# Smart_Light_Panel3.net
KiCad netlist of a schematic drawn in EAGLE
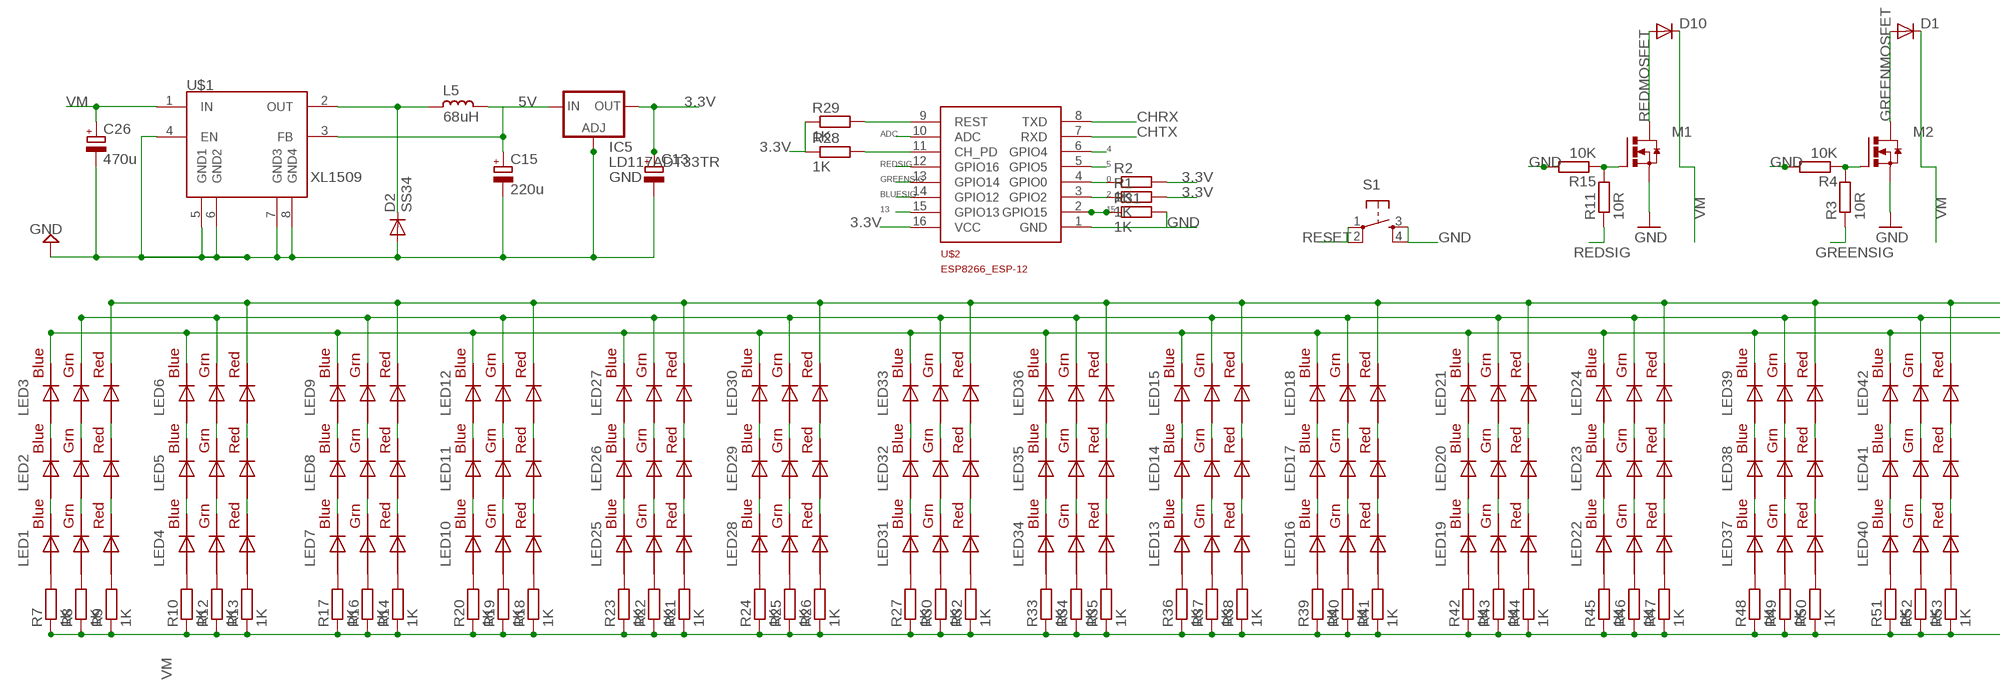
[diagram p0: schematic, sheet 1, part 1 of 2]
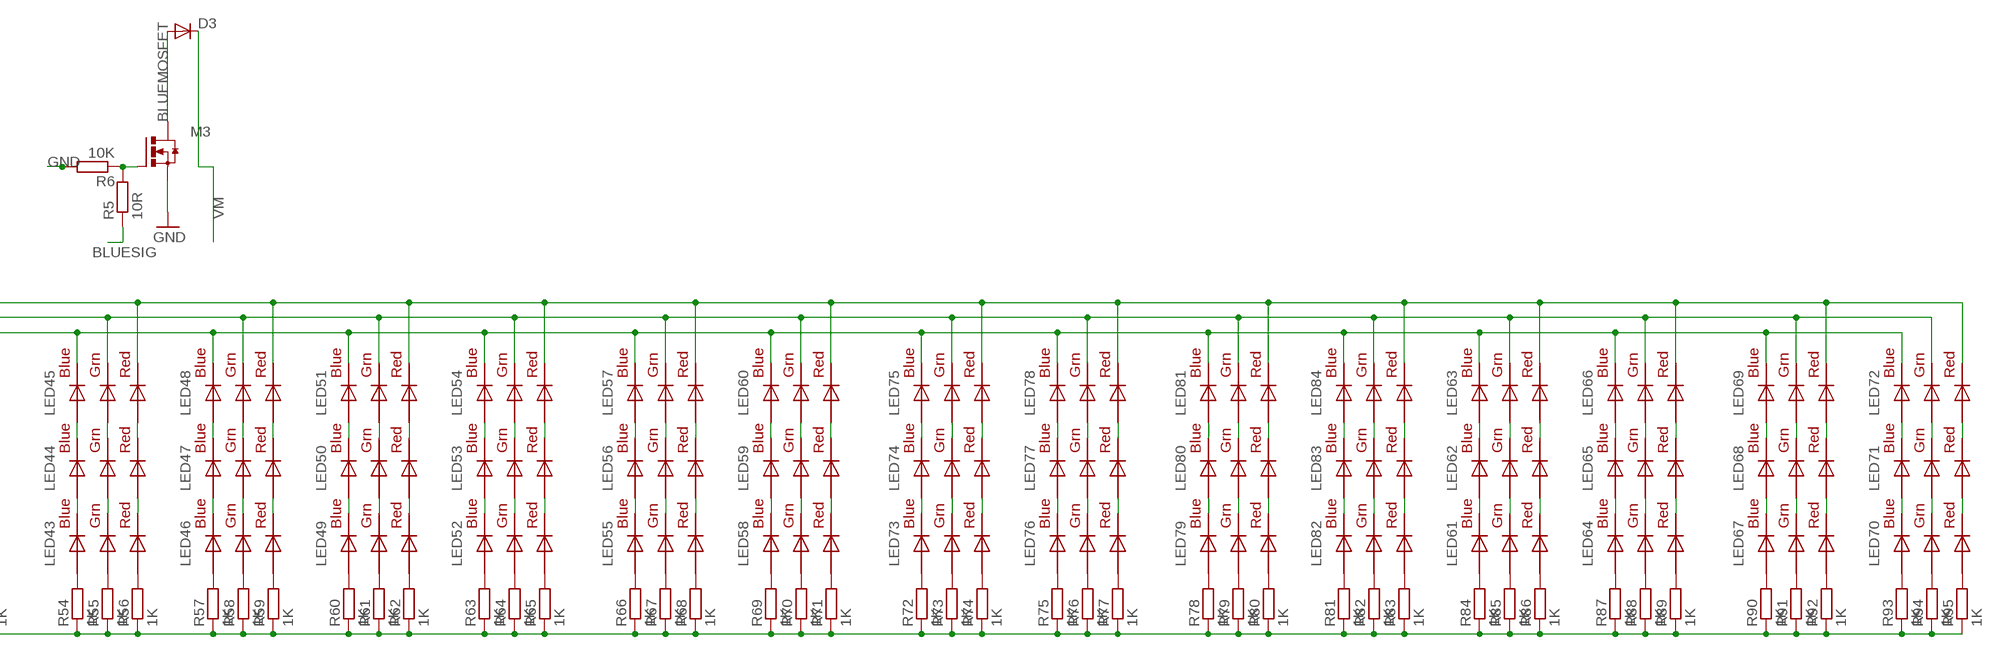
[diagram p1: schematic, sheet 1, part 2 of 2]

(export (version "E")
  (design (tool "Eeschema 10.0.6"))
  (components
    (comp (ref "C13")
      (value "CPOL-EUE2.5-7")
      (footprint "eagle-import:E2,5-7")
      (libsource (lib "eagle-import") (part "CPOL-EUE2.5-7"))
    )
    (comp (ref "C15")
      (value "220u")
      (footprint "eagle-import:E2,5-7")
      (libsource (lib "eagle-import") (part "CPOL-EUE2.5-7"))
    )
    (comp (ref "C26")
      (value "470u")
      (footprint "eagle-import:E2,5-7")
      (libsource (lib "eagle-import") (part "CPOL-EUE2.5-7"))
    )
    (comp (ref "D1")
      (value "DIODESMA-ALT")
      (footprint "eagle-import:SMA-DIODE_ALT")
      (libsource (lib "eagle-import") (part "DIODESMA-ALT"))
    )
    (comp (ref "D2")
      (value "SS34")
      (footprint "eagle-import:DO-214AC")
      (libsource (lib "eagle-import") (part "DIODE-DO-214AC"))
    )
    (comp (ref "D3")
      (value "DIODESMA-ALT")
      (footprint "eagle-import:SMA-DIODE_ALT")
      (libsource (lib "eagle-import") (part "DIODESMA-ALT"))
    )
    (comp (ref "D10")
      (value "DIODESMA-ALT")
      (footprint "eagle-import:SMA-DIODE_ALT")
      (libsource (lib "eagle-import") (part "DIODESMA-ALT"))
    )
    (comp (ref "IC5")
      (value "LD117ADT33TR")
      (footprint "eagle-import:DPACK")
      (libsource (lib "eagle-import") (part "LD117A?DT33TR"))
    )
    (comp (ref "L5")
      (value "68uH")
      (footprint "eagle-import:CD75")
      (libsource (lib "eagle-import") (part "L_CD75"))
    )
    (comp (ref "LED1")
      (value "RGBLED5050")
      (footprint "eagle-import:RGBLED5050")
      (libsource (lib "eagle-import") (part "RGBLED5050"))
    )
    (comp (ref "LED2")
      (value "RGBLED5050")
      (footprint "eagle-import:RGBLED5050")
      (libsource (lib "eagle-import") (part "RGBLED5050"))
    )
    (comp (ref "LED3")
      (value "RGBLED5050")
      (footprint "eagle-import:RGBLED5050")
      (libsource (lib "eagle-import") (part "RGBLED5050"))
    )
    (comp (ref "LED4")
      (value "RGBLED5050")
      (footprint "eagle-import:RGBLED5050")
      (libsource (lib "eagle-import") (part "RGBLED5050"))
    )
    (comp (ref "LED5")
      (value "RGBLED5050")
      (footprint "eagle-import:RGBLED5050")
      (libsource (lib "eagle-import") (part "RGBLED5050"))
    )
    (comp (ref "LED6")
      (value "RGBLED5050")
      (footprint "eagle-import:RGBLED5050")
      (libsource (lib "eagle-import") (part "RGBLED5050"))
    )
    (comp (ref "LED7")
      (value "RGBLED5050")
      (footprint "eagle-import:RGBLED5050")
      (libsource (lib "eagle-import") (part "RGBLED5050"))
    )
    (comp (ref "LED8")
      (value "RGBLED5050")
      (footprint "eagle-import:RGBLED5050")
      (libsource (lib "eagle-import") (part "RGBLED5050"))
    )
    (comp (ref "LED9")
      (value "RGBLED5050")
      (footprint "eagle-import:RGBLED5050")
      (libsource (lib "eagle-import") (part "RGBLED5050"))
    )
    (comp (ref "LED10")
      (value "RGBLED5050")
      (footprint "eagle-import:RGBLED5050")
      (libsource (lib "eagle-import") (part "RGBLED5050"))
    )
    (comp (ref "LED11")
      (value "RGBLED5050")
      (footprint "eagle-import:RGBLED5050")
      (libsource (lib "eagle-import") (part "RGBLED5050"))
    )
    (comp (ref "LED12")
      (value "RGBLED5050")
      (footprint "eagle-import:RGBLED5050")
      (libsource (lib "eagle-import") (part "RGBLED5050"))
    )
    (comp (ref "LED13")
      (value "RGBLED5050")
      (footprint "eagle-import:RGBLED5050")
      (libsource (lib "eagle-import") (part "RGBLED5050"))
    )
    (comp (ref "LED14")
      (value "RGBLED5050")
      (footprint "eagle-import:RGBLED5050")
      (libsource (lib "eagle-import") (part "RGBLED5050"))
    )
    (comp (ref "LED15")
      (value "RGBLED5050")
      (footprint "eagle-import:RGBLED5050")
      (libsource (lib "eagle-import") (part "RGBLED5050"))
    )
    (comp (ref "LED16")
      (value "RGBLED5050")
      (footprint "eagle-import:RGBLED5050")
      (libsource (lib "eagle-import") (part "RGBLED5050"))
    )
    (comp (ref "LED17")
      (value "RGBLED5050")
      (footprint "eagle-import:RGBLED5050")
      (libsource (lib "eagle-import") (part "RGBLED5050"))
    )
    (comp (ref "LED18")
      (value "RGBLED5050")
      (footprint "eagle-import:RGBLED5050")
      (libsource (lib "eagle-import") (part "RGBLED5050"))
    )
    (comp (ref "LED19")
      (value "RGBLED5050")
      (footprint "eagle-import:RGBLED5050")
      (libsource (lib "eagle-import") (part "RGBLED5050"))
    )
    (comp (ref "LED20")
      (value "RGBLED5050")
      (footprint "eagle-import:RGBLED5050")
      (libsource (lib "eagle-import") (part "RGBLED5050"))
    )
    (comp (ref "LED21")
      (value "RGBLED5050")
      (footprint "eagle-import:RGBLED5050")
      (libsource (lib "eagle-import") (part "RGBLED5050"))
    )
    (comp (ref "LED22")
      (value "RGBLED5050")
      (footprint "eagle-import:RGBLED5050")
      (libsource (lib "eagle-import") (part "RGBLED5050"))
    )
    (comp (ref "LED23")
      (value "RGBLED5050")
      (footprint "eagle-import:RGBLED5050")
      (libsource (lib "eagle-import") (part "RGBLED5050"))
    )
    (comp (ref "LED24")
      (value "RGBLED5050")
      (footprint "eagle-import:RGBLED5050")
      (libsource (lib "eagle-import") (part "RGBLED5050"))
    )
    (comp (ref "LED25")
      (value "RGBLED5050")
      (footprint "eagle-import:RGBLED5050")
      (libsource (lib "eagle-import") (part "RGBLED5050"))
    )
    (comp (ref "LED26")
      (value "RGBLED5050")
      (footprint "eagle-import:RGBLED5050")
      (libsource (lib "eagle-import") (part "RGBLED5050"))
    )
    (comp (ref "LED27")
      (value "RGBLED5050")
      (footprint "eagle-import:RGBLED5050")
      (libsource (lib "eagle-import") (part "RGBLED5050"))
    )
    (comp (ref "LED28")
      (value "RGBLED5050")
      (footprint "eagle-import:RGBLED5050")
      (libsource (lib "eagle-import") (part "RGBLED5050"))
    )
    (comp (ref "LED29")
      (value "RGBLED5050")
      (footprint "eagle-import:RGBLED5050")
      (libsource (lib "eagle-import") (part "RGBLED5050"))
    )
    (comp (ref "LED30")
      (value "RGBLED5050")
      (footprint "eagle-import:RGBLED5050")
      (libsource (lib "eagle-import") (part "RGBLED5050"))
    )
    (comp (ref "LED31")
      (value "RGBLED5050")
      (footprint "eagle-import:RGBLED5050")
      (libsource (lib "eagle-import") (part "RGBLED5050"))
    )
    (comp (ref "LED32")
      (value "RGBLED5050")
      (footprint "eagle-import:RGBLED5050")
      (libsource (lib "eagle-import") (part "RGBLED5050"))
    )
    (comp (ref "LED33")
      (value "RGBLED5050")
      (footprint "eagle-import:RGBLED5050")
      (libsource (lib "eagle-import") (part "RGBLED5050"))
    )
    (comp (ref "LED34")
      (value "RGBLED5050")
      (footprint "eagle-import:RGBLED5050")
      (libsource (lib "eagle-import") (part "RGBLED5050"))
    )
    (comp (ref "LED35")
      (value "RGBLED5050")
      (footprint "eagle-import:RGBLED5050")
      (libsource (lib "eagle-import") (part "RGBLED5050"))
    )
    (comp (ref "LED36")
      (value "RGBLED5050")
      (footprint "eagle-import:RGBLED5050")
      (libsource (lib "eagle-import") (part "RGBLED5050"))
    )
    (comp (ref "LED37")
      (value "RGBLED5050")
      (footprint "eagle-import:RGBLED5050")
      (libsource (lib "eagle-import") (part "RGBLED5050"))
    )
    (comp (ref "LED38")
      (value "RGBLED5050")
      (footprint "eagle-import:RGBLED5050")
      (libsource (lib "eagle-import") (part "RGBLED5050"))
    )
    (comp (ref "LED39")
      (value "RGBLED5050")
      (footprint "eagle-import:RGBLED5050")
      (libsource (lib "eagle-import") (part "RGBLED5050"))
    )
    (comp (ref "LED40")
      (value "RGBLED5050")
      (footprint "eagle-import:RGBLED5050")
      (libsource (lib "eagle-import") (part "RGBLED5050"))
    )
    (comp (ref "LED41")
      (value "RGBLED5050")
      (footprint "eagle-import:RGBLED5050")
      (libsource (lib "eagle-import") (part "RGBLED5050"))
    )
    (comp (ref "LED42")
      (value "RGBLED5050")
      (footprint "eagle-import:RGBLED5050")
      (libsource (lib "eagle-import") (part "RGBLED5050"))
    )
    (comp (ref "LED43")
      (value "RGBLED5050")
      (footprint "eagle-import:RGBLED5050")
      (libsource (lib "eagle-import") (part "RGBLED5050"))
    )
    (comp (ref "LED44")
      (value "RGBLED5050")
      (footprint "eagle-import:RGBLED5050")
      (libsource (lib "eagle-import") (part "RGBLED5050"))
    )
    (comp (ref "LED45")
      (value "RGBLED5050")
      (footprint "eagle-import:RGBLED5050")
      (libsource (lib "eagle-import") (part "RGBLED5050"))
    )
    (comp (ref "LED46")
      (value "RGBLED5050")
      (footprint "eagle-import:RGBLED5050")
      (libsource (lib "eagle-import") (part "RGBLED5050"))
    )
    (comp (ref "LED47")
      (value "RGBLED5050")
      (footprint "eagle-import:RGBLED5050")
      (libsource (lib "eagle-import") (part "RGBLED5050"))
    )
    (comp (ref "LED48")
      (value "RGBLED5050")
      (footprint "eagle-import:RGBLED5050")
      (libsource (lib "eagle-import") (part "RGBLED5050"))
    )
    (comp (ref "LED49")
      (value "RGBLED5050")
      (footprint "eagle-import:RGBLED5050")
      (libsource (lib "eagle-import") (part "RGBLED5050"))
    )
    (comp (ref "LED50")
      (value "RGBLED5050")
      (footprint "eagle-import:RGBLED5050")
      (libsource (lib "eagle-import") (part "RGBLED5050"))
    )
    (comp (ref "LED51")
      (value "RGBLED5050")
      (footprint "eagle-import:RGBLED5050")
      (libsource (lib "eagle-import") (part "RGBLED5050"))
    )
    (comp (ref "LED52")
      (value "RGBLED5050")
      (footprint "eagle-import:RGBLED5050")
      (libsource (lib "eagle-import") (part "RGBLED5050"))
    )
    (comp (ref "LED53")
      (value "RGBLED5050")
      (footprint "eagle-import:RGBLED5050")
      (libsource (lib "eagle-import") (part "RGBLED5050"))
    )
    (comp (ref "LED54")
      (value "RGBLED5050")
      (footprint "eagle-import:RGBLED5050")
      (libsource (lib "eagle-import") (part "RGBLED5050"))
    )
    (comp (ref "LED55")
      (value "RGBLED5050")
      (footprint "eagle-import:RGBLED5050")
      (libsource (lib "eagle-import") (part "RGBLED5050"))
    )
    (comp (ref "LED56")
      (value "RGBLED5050")
      (footprint "eagle-import:RGBLED5050")
      (libsource (lib "eagle-import") (part "RGBLED5050"))
    )
    (comp (ref "LED57")
      (value "RGBLED5050")
      (footprint "eagle-import:RGBLED5050")
      (libsource (lib "eagle-import") (part "RGBLED5050"))
    )
    (comp (ref "LED58")
      (value "RGBLED5050")
      (footprint "eagle-import:RGBLED5050")
      (libsource (lib "eagle-import") (part "RGBLED5050"))
    )
    (comp (ref "LED59")
      (value "RGBLED5050")
      (footprint "eagle-import:RGBLED5050")
      (libsource (lib "eagle-import") (part "RGBLED5050"))
    )
    (comp (ref "LED60")
      (value "RGBLED5050")
      (footprint "eagle-import:RGBLED5050")
      (libsource (lib "eagle-import") (part "RGBLED5050"))
    )
    (comp (ref "LED61")
      (value "RGBLED5050")
      (footprint "eagle-import:RGBLED5050")
      (libsource (lib "eagle-import") (part "RGBLED5050"))
    )
    (comp (ref "LED62")
      (value "RGBLED5050")
      (footprint "eagle-import:RGBLED5050")
      (libsource (lib "eagle-import") (part "RGBLED5050"))
    )
    (comp (ref "LED63")
      (value "RGBLED5050")
      (footprint "eagle-import:RGBLED5050")
      (libsource (lib "eagle-import") (part "RGBLED5050"))
    )
    (comp (ref "LED64")
      (value "RGBLED5050")
      (footprint "eagle-import:RGBLED5050")
      (libsource (lib "eagle-import") (part "RGBLED5050"))
    )
    (comp (ref "LED65")
      (value "RGBLED5050")
      (footprint "eagle-import:RGBLED5050")
      (libsource (lib "eagle-import") (part "RGBLED5050"))
    )
    (comp (ref "LED66")
      (value "RGBLED5050")
      (footprint "eagle-import:RGBLED5050")
      (libsource (lib "eagle-import") (part "RGBLED5050"))
    )
    (comp (ref "LED67")
      (value "RGBLED5050")
      (footprint "eagle-import:RGBLED5050")
      (libsource (lib "eagle-import") (part "RGBLED5050"))
    )
    (comp (ref "LED68")
      (value "RGBLED5050")
      (footprint "eagle-import:RGBLED5050")
      (libsource (lib "eagle-import") (part "RGBLED5050"))
    )
    (comp (ref "LED69")
      (value "RGBLED5050")
      (footprint "eagle-import:RGBLED5050")
      (libsource (lib "eagle-import") (part "RGBLED5050"))
    )
    (comp (ref "LED70")
      (value "RGBLED5050")
      (footprint "eagle-import:RGBLED5050")
      (libsource (lib "eagle-import") (part "RGBLED5050"))
    )
    (comp (ref "LED71")
      (value "RGBLED5050")
      (footprint "eagle-import:RGBLED5050")
      (libsource (lib "eagle-import") (part "RGBLED5050"))
    )
    (comp (ref "LED72")
      (value "RGBLED5050")
      (footprint "eagle-import:RGBLED5050")
      (libsource (lib "eagle-import") (part "RGBLED5050"))
    )
    (comp (ref "LED73")
      (value "RGBLED5050")
      (footprint "eagle-import:RGBLED5050")
      (libsource (lib "eagle-import") (part "RGBLED5050"))
    )
    (comp (ref "LED74")
      (value "RGBLED5050")
      (footprint "eagle-import:RGBLED5050")
      (libsource (lib "eagle-import") (part "RGBLED5050"))
    )
    (comp (ref "LED75")
      (value "RGBLED5050")
      (footprint "eagle-import:RGBLED5050")
      (libsource (lib "eagle-import") (part "RGBLED5050"))
    )
    (comp (ref "LED76")
      (value "RGBLED5050")
      (footprint "eagle-import:RGBLED5050")
      (libsource (lib "eagle-import") (part "RGBLED5050"))
    )
    (comp (ref "LED77")
      (value "RGBLED5050")
      (footprint "eagle-import:RGBLED5050")
      (libsource (lib "eagle-import") (part "RGBLED5050"))
    )
    (comp (ref "LED78")
      (value "RGBLED5050")
      (footprint "eagle-import:RGBLED5050")
      (libsource (lib "eagle-import") (part "RGBLED5050"))
    )
    (comp (ref "LED79")
      (value "RGBLED5050")
      (footprint "eagle-import:RGBLED5050")
      (libsource (lib "eagle-import") (part "RGBLED5050"))
    )
    (comp (ref "LED80")
      (value "RGBLED5050")
      (footprint "eagle-import:RGBLED5050")
      (libsource (lib "eagle-import") (part "RGBLED5050"))
    )
    (comp (ref "LED81")
      (value "RGBLED5050")
      (footprint "eagle-import:RGBLED5050")
      (libsource (lib "eagle-import") (part "RGBLED5050"))
    )
    (comp (ref "LED82")
      (value "RGBLED5050")
      (footprint "eagle-import:RGBLED5050")
      (libsource (lib "eagle-import") (part "RGBLED5050"))
    )
    (comp (ref "LED83")
      (value "RGBLED5050")
      (footprint "eagle-import:RGBLED5050")
      (libsource (lib "eagle-import") (part "RGBLED5050"))
    )
    (comp (ref "LED84")
      (value "RGBLED5050")
      (footprint "eagle-import:RGBLED5050")
      (libsource (lib "eagle-import") (part "RGBLED5050"))
    )
    (comp (ref "M1")
      (value "IRLR024N")
      (footprint "eagle-import:TO252")
      (libsource (lib "eagle-import") (part "IRLR024N"))
    )
    (comp (ref "M2")
      (value "IRLR024N")
      (footprint "eagle-import:TO252")
      (libsource (lib "eagle-import") (part "IRLR024N"))
    )
    (comp (ref "M3")
      (value "IRLR024N")
      (footprint "eagle-import:TO252")
      (libsource (lib "eagle-import") (part "IRLR024N"))
    )
    (comp (ref "R1")
      (value "1K")
      (footprint "eagle-import:M1206")
      (libsource (lib "eagle-import") (part "R-EU_M1206"))
    )
    (comp (ref "R2")
      (value "1K")
      (footprint "eagle-import:M1206")
      (libsource (lib "eagle-import") (part "R-EU_M1206"))
    )
    (comp (ref "R3")
      (value "10R")
      (footprint "eagle-import:M1206")
      (libsource (lib "eagle-import") (part "resistor_R-EU_M1206"))
    )
    (comp (ref "R4")
      (value "10K")
      (footprint "eagle-import:M1206")
      (libsource (lib "eagle-import") (part "resistor_R-EU_M1206"))
    )
    (comp (ref "R5")
      (value "10R")
      (footprint "eagle-import:M1206")
      (libsource (lib "eagle-import") (part "resistor_R-EU_M1206"))
    )
    (comp (ref "R6")
      (value "10K")
      (footprint "eagle-import:M1206")
      (libsource (lib "eagle-import") (part "resistor_R-EU_M1206"))
    )
    (comp (ref "R7")
      (value "1K")
      (footprint "eagle-import:R0603")
      (libsource (lib "eagle-import") (part "R-EU_R0603"))
    )
    (comp (ref "R8")
      (value "1K")
      (footprint "eagle-import:R0603")
      (libsource (lib "eagle-import") (part "R-EU_R0603"))
    )
    (comp (ref "R9")
      (value "1K")
      (footprint "eagle-import:R0603")
      (libsource (lib "eagle-import") (part "R-EU_R0603"))
    )
    (comp (ref "R10")
      (value "1K")
      (footprint "eagle-import:R0603")
      (libsource (lib "eagle-import") (part "R-EU_R0603"))
    )
    (comp (ref "R11")
      (value "10R")
      (footprint "eagle-import:M1206")
      (libsource (lib "eagle-import") (part "resistor_R-EU_M1206"))
    )
    (comp (ref "R12")
      (value "1K")
      (footprint "eagle-import:R0603")
      (libsource (lib "eagle-import") (part "R-EU_R0603"))
    )
    (comp (ref "R13")
      (value "1K")
      (footprint "eagle-import:R0603")
      (libsource (lib "eagle-import") (part "R-EU_R0603"))
    )
    (comp (ref "R14")
      (value "1K")
      (footprint "eagle-import:R0603")
      (libsource (lib "eagle-import") (part "R-EU_R0603"))
    )
    (comp (ref "R15")
      (value "10K")
      (footprint "eagle-import:M1206")
      (libsource (lib "eagle-import") (part "resistor_R-EU_M1206"))
    )
    (comp (ref "R16")
      (value "1K")
      (footprint "eagle-import:R0603")
      (libsource (lib "eagle-import") (part "R-EU_R0603"))
    )
    (comp (ref "R17")
      (value "1K")
      (footprint "eagle-import:R0603")
      (libsource (lib "eagle-import") (part "R-EU_R0603"))
    )
    (comp (ref "R18")
      (value "1K")
      (footprint "eagle-import:R0603")
      (libsource (lib "eagle-import") (part "R-EU_R0603"))
    )
    (comp (ref "R19")
      (value "1K")
      (footprint "eagle-import:R0603")
      (libsource (lib "eagle-import") (part "R-EU_R0603"))
    )
    (comp (ref "R20")
      (value "1K")
      (footprint "eagle-import:R0603")
      (libsource (lib "eagle-import") (part "R-EU_R0603"))
    )
    (comp (ref "R21")
      (value "1K")
      (footprint "eagle-import:R0603")
      (libsource (lib "eagle-import") (part "R-EU_R0603"))
    )
    (comp (ref "R22")
      (value "1K")
      (footprint "eagle-import:R0603")
      (libsource (lib "eagle-import") (part "R-EU_R0603"))
    )
    (comp (ref "R23")
      (value "1K")
      (footprint "eagle-import:R0603")
      (libsource (lib "eagle-import") (part "R-EU_R0603"))
    )
    (comp (ref "R24")
      (value "1K")
      (footprint "eagle-import:R0603")
      (libsource (lib "eagle-import") (part "R-EU_R0603"))
    )
    (comp (ref "R25")
      (value "1K")
      (footprint "eagle-import:R0603")
      (libsource (lib "eagle-import") (part "R-EU_R0603"))
    )
    (comp (ref "R26")
      (value "1K")
      (footprint "eagle-import:R0603")
      (libsource (lib "eagle-import") (part "R-EU_R0603"))
    )
    (comp (ref "R27")
      (value "1K")
      (footprint "eagle-import:R0603")
      (libsource (lib "eagle-import") (part "R-EU_R0603"))
    )
    (comp (ref "R28")
      (value "1K")
      (footprint "eagle-import:M1206")
      (libsource (lib "eagle-import") (part "R-EU_M1206"))
    )
    (comp (ref "R29")
      (value "1K")
      (footprint "eagle-import:M1206")
      (libsource (lib "eagle-import") (part "R-EU_M1206"))
    )
    (comp (ref "R30")
      (value "1K")
      (footprint "eagle-import:R0603")
      (libsource (lib "eagle-import") (part "R-EU_R0603"))
    )
    (comp (ref "R31")
      (value "1K")
      (footprint "eagle-import:M1206")
      (libsource (lib "eagle-import") (part "R-EU_M1206"))
    )
    (comp (ref "R32")
      (value "1K")
      (footprint "eagle-import:R0603")
      (libsource (lib "eagle-import") (part "R-EU_R0603"))
    )
    (comp (ref "R33")
      (value "1K")
      (footprint "eagle-import:R0603")
      (libsource (lib "eagle-import") (part "R-EU_R0603"))
    )
    (comp (ref "R34")
      (value "1K")
      (footprint "eagle-import:R0603")
      (libsource (lib "eagle-import") (part "R-EU_R0603"))
    )
    (comp (ref "R35")
      (value "1K")
      (footprint "eagle-import:R0603")
      (libsource (lib "eagle-import") (part "R-EU_R0603"))
    )
    (comp (ref "R36")
      (value "1K")
      (footprint "eagle-import:R0603")
      (libsource (lib "eagle-import") (part "R-EU_R0603"))
    )
    (comp (ref "R37")
      (value "1K")
      (footprint "eagle-import:R0603")
      (libsource (lib "eagle-import") (part "R-EU_R0603"))
    )
    (comp (ref "R38")
      (value "1K")
      (footprint "eagle-import:R0603")
      (libsource (lib "eagle-import") (part "R-EU_R0603"))
    )
    (comp (ref "R39")
      (value "1K")
      (footprint "eagle-import:R0603")
      (libsource (lib "eagle-import") (part "R-EU_R0603"))
    )
    (comp (ref "R40")
      (value "1K")
      (footprint "eagle-import:R0603")
      (libsource (lib "eagle-import") (part "R-EU_R0603"))
    )
    (comp (ref "R41")
      (value "1K")
      (footprint "eagle-import:R0603")
      (libsource (lib "eagle-import") (part "R-EU_R0603"))
    )
    (comp (ref "R42")
      (value "1K")
      (footprint "eagle-import:R0603")
      (libsource (lib "eagle-import") (part "R-EU_R0603"))
    )
    (comp (ref "R43")
      (value "1K")
      (footprint "eagle-import:R0603")
      (libsource (lib "eagle-import") (part "R-EU_R0603"))
    )
    (comp (ref "R44")
      (value "1K")
      (footprint "eagle-import:R0603")
      (libsource (lib "eagle-import") (part "R-EU_R0603"))
    )
    (comp (ref "R45")
      (value "1K")
      (footprint "eagle-import:R0603")
      (libsource (lib "eagle-import") (part "R-EU_R0603"))
    )
    (comp (ref "R46")
      (value "1K")
      (footprint "eagle-import:R0603")
      (libsource (lib "eagle-import") (part "R-EU_R0603"))
    )
    (comp (ref "R47")
      (value "1K")
      (footprint "eagle-import:R0603")
      (libsource (lib "eagle-import") (part "R-EU_R0603"))
    )
    (comp (ref "R48")
      (value "1K")
      (footprint "eagle-import:R0603")
      (libsource (lib "eagle-import") (part "R-EU_R0603"))
    )
    (comp (ref "R49")
      (value "1K")
      (footprint "eagle-import:R0603")
      (libsource (lib "eagle-import") (part "R-EU_R0603"))
    )
    (comp (ref "R50")
      (value "1K")
      (footprint "eagle-import:R0603")
      (libsource (lib "eagle-import") (part "R-EU_R0603"))
    )
    (comp (ref "R51")
      (value "1K")
      (footprint "eagle-import:R0603")
      (libsource (lib "eagle-import") (part "R-EU_R0603"))
    )
    (comp (ref "R52")
      (value "1K")
      (footprint "eagle-import:R0603")
      (libsource (lib "eagle-import") (part "R-EU_R0603"))
    )
    (comp (ref "R53")
      (value "1K")
      (footprint "eagle-import:R0603")
      (libsource (lib "eagle-import") (part "R-EU_R0603"))
    )
    (comp (ref "R54")
      (value "1K")
      (footprint "eagle-import:R0603")
      (libsource (lib "eagle-import") (part "R-EU_R0603"))
    )
    (comp (ref "R55")
      (value "1K")
      (footprint "eagle-import:R0603")
      (libsource (lib "eagle-import") (part "R-EU_R0603"))
    )
    (comp (ref "R56")
      (value "1K")
      (footprint "eagle-import:R0603")
      (libsource (lib "eagle-import") (part "R-EU_R0603"))
    )
    (comp (ref "R57")
      (value "1K")
      (footprint "eagle-import:R0603")
      (libsource (lib "eagle-import") (part "R-EU_R0603"))
    )
    (comp (ref "R58")
      (value "1K")
      (footprint "eagle-import:R0603")
      (libsource (lib "eagle-import") (part "R-EU_R0603"))
    )
    (comp (ref "R59")
      (value "1K")
      (footprint "eagle-import:R0603")
      (libsource (lib "eagle-import") (part "R-EU_R0603"))
    )
    (comp (ref "R60")
      (value "1K")
      (footprint "eagle-import:R0603")
      (libsource (lib "eagle-import") (part "R-EU_R0603"))
    )
    (comp (ref "R61")
      (value "1K")
      (footprint "eagle-import:R0603")
      (libsource (lib "eagle-import") (part "R-EU_R0603"))
    )
    (comp (ref "R62")
      (value "1K")
      (footprint "eagle-import:R0603")
      (libsource (lib "eagle-import") (part "R-EU_R0603"))
    )
    (comp (ref "R63")
      (value "1K")
      (footprint "eagle-import:R0603")
      (libsource (lib "eagle-import") (part "R-EU_R0603"))
    )
    (comp (ref "R64")
      (value "1K")
      (footprint "eagle-import:R0603")
      (libsource (lib "eagle-import") (part "R-EU_R0603"))
    )
    (comp (ref "R65")
      (value "1K")
      (footprint "eagle-import:R0603")
      (libsource (lib "eagle-import") (part "R-EU_R0603"))
    )
    (comp (ref "R66")
      (value "1K")
      (footprint "eagle-import:R0603")
      (libsource (lib "eagle-import") (part "R-EU_R0603"))
    )
    (comp (ref "R67")
      (value "1K")
      (footprint "eagle-import:R0603")
      (libsource (lib "eagle-import") (part "R-EU_R0603"))
    )
    (comp (ref "R68")
      (value "1K")
      (footprint "eagle-import:R0603")
      (libsource (lib "eagle-import") (part "R-EU_R0603"))
    )
    (comp (ref "R69")
      (value "1K")
      (footprint "eagle-import:R0603")
      (libsource (lib "eagle-import") (part "R-EU_R0603"))
    )
    (comp (ref "R70")
      (value "1K")
      (footprint "eagle-import:R0603")
      (libsource (lib "eagle-import") (part "R-EU_R0603"))
    )
    (comp (ref "R71")
      (value "1K")
      (footprint "eagle-import:R0603")
      (libsource (lib "eagle-import") (part "R-EU_R0603"))
    )
    (comp (ref "R72")
      (value "1K")
      (footprint "eagle-import:R0603")
      (libsource (lib "eagle-import") (part "R-EU_R0603"))
    )
    (comp (ref "R73")
      (value "1K")
      (footprint "eagle-import:R0603")
      (libsource (lib "eagle-import") (part "R-EU_R0603"))
    )
    (comp (ref "R74")
      (value "1K")
      (footprint "eagle-import:R0603")
      (libsource (lib "eagle-import") (part "R-EU_R0603"))
    )
    (comp (ref "R75")
      (value "1K")
      (footprint "eagle-import:R0603")
      (libsource (lib "eagle-import") (part "R-EU_R0603"))
    )
    (comp (ref "R76")
      (value "1K")
      (footprint "eagle-import:R0603")
      (libsource (lib "eagle-import") (part "R-EU_R0603"))
    )
    (comp (ref "R77")
      (value "1K")
      (footprint "eagle-import:R0603")
      (libsource (lib "eagle-import") (part "R-EU_R0603"))
    )
    (comp (ref "R78")
      (value "1K")
      (footprint "eagle-import:R0603")
      (libsource (lib "eagle-import") (part "R-EU_R0603"))
    )
    (comp (ref "R79")
      (value "1K")
      (footprint "eagle-import:R0603")
      (libsource (lib "eagle-import") (part "R-EU_R0603"))
    )
    (comp (ref "R80")
      (value "1K")
      (footprint "eagle-import:R0603")
      (libsource (lib "eagle-import") (part "R-EU_R0603"))
    )
    (comp (ref "R81")
      (value "1K")
      (footprint "eagle-import:R0603")
      (libsource (lib "eagle-import") (part "R-EU_R0603"))
    )
    (comp (ref "R82")
      (value "1K")
      (footprint "eagle-import:R0603")
      (libsource (lib "eagle-import") (part "R-EU_R0603"))
    )
    (comp (ref "R83")
      (value "1K")
      (footprint "eagle-import:R0603")
      (libsource (lib "eagle-import") (part "R-EU_R0603"))
    )
    (comp (ref "R84")
      (value "1K")
      (footprint "eagle-import:R0603")
      (libsource (lib "eagle-import") (part "R-EU_R0603"))
    )
    (comp (ref "R85")
      (value "1K")
      (footprint "eagle-import:R0603")
      (libsource (lib "eagle-import") (part "R-EU_R0603"))
    )
    (comp (ref "R86")
      (value "1K")
      (footprint "eagle-import:R0603")
      (libsource (lib "eagle-import") (part "R-EU_R0603"))
    )
    (comp (ref "R87")
      (value "1K")
      (footprint "eagle-import:R0603")
      (libsource (lib "eagle-import") (part "R-EU_R0603"))
    )
    (comp (ref "R88")
      (value "1K")
      (footprint "eagle-import:R0603")
      (libsource (lib "eagle-import") (part "R-EU_R0603"))
    )
    (comp (ref "R89")
      (value "1K")
      (footprint "eagle-import:R0603")
      (libsource (lib "eagle-import") (part "R-EU_R0603"))
    )
    (comp (ref "R90")
      (value "1K")
      (footprint "eagle-import:R0603")
      (libsource (lib "eagle-import") (part "R-EU_R0603"))
    )
    (comp (ref "R91")
      (value "1K")
      (footprint "eagle-import:R0603")
      (libsource (lib "eagle-import") (part "R-EU_R0603"))
    )
    (comp (ref "R92")
      (value "1K")
      (footprint "eagle-import:R0603")
      (libsource (lib "eagle-import") (part "R-EU_R0603"))
    )
    (comp (ref "R93")
      (value "1K")
      (footprint "eagle-import:R0603")
      (libsource (lib "eagle-import") (part "R-EU_R0603"))
    )
    (comp (ref "R94")
      (value "1K")
      (footprint "eagle-import:R0603")
      (libsource (lib "eagle-import") (part "R-EU_R0603"))
    )
    (comp (ref "R95")
      (value "1K")
      (footprint "eagle-import:R0603")
      (libsource (lib "eagle-import") (part "R-EU_R0603"))
    )
    (comp (ref "S1")
      (value "TAC_SWITCHPTH")
      (footprint "eagle-import:TACTILE-PTH")
      (libsource (lib "eagle-import") (part "TAC_SWITCHPTH"))
    )
    (comp (ref "U$1")
      (value "XL1509")
      (footprint "eagle-import:SO08")
      (libsource (lib "eagle-import") (part "XL1509"))
    )
    (comp (ref "U$2")
      (value "ESP8266_ESP-12")
      (footprint "eagle-import:ESP8266-ESP12")
      (libsource (lib "eagle-import") (part "ESP8266_ESP-12"))
    )
  )
  (nets
    (net (code "1") (name "/0") (class "Default")
      (node (ref "R2") (pin "1") (pinfunction "1_1") (pintype "passive"))
      (node (ref "U$2") (pin "4") (pinfunction "GPIO0_4") (pintype "bidirectional"))
    )
    (net (code "2") (name "/2") (class "Default")
      (node (ref "R1") (pin "1") (pinfunction "1_1") (pintype "passive"))
      (node (ref "U$2") (pin "3") (pinfunction "GPIO2_3") (pintype "bidirectional"))
    )
    (net (code "3") (name "/3.3V") (class "Default")
      (node (ref "C13") (pin "+") (pinfunction "+_+") (pintype "passive"))
      (node (ref "IC5") (pin "4") (pinfunction "OUT_4") (pintype "passive"))
      (node (ref "R1") (pin "2") (pinfunction "2_2") (pintype "passive"))
      (node (ref "R2") (pin "2") (pinfunction "2_2") (pintype "passive"))
      (node (ref "R28") (pin "1") (pinfunction "1_1") (pintype "passive"))
      (node (ref "R29") (pin "1") (pinfunction "1_1") (pintype "passive"))
      (node (ref "U$2") (pin "16") (pinfunction "VCC_16") (pintype "bidirectional"))
    )
    (net (code "4") (name "/4") (class "Default")
      (node (ref "U$2") (pin "6") (pinfunction "GPIO4_6") (pintype "bidirectional"))
    )
    (net (code "5") (name "/5") (class "Default")
      (node (ref "U$2") (pin "5") (pinfunction "GPIO5_5") (pintype "bidirectional"))
    )
    (net (code "6") (name "/5V") (class "Default")
      (node (ref "C15") (pin "+") (pinfunction "+_+") (pintype "passive"))
      (node (ref "IC5") (pin "3") (pinfunction "IN_3") (pintype "input"))
      (node (ref "L5") (pin "1") (pinfunction "1_1") (pintype "passive"))
      (node (ref "U$1") (pin "3") (pinfunction "FB_3") (pintype "bidirectional"))
    )
    (net (code "7") (name "/13") (class "Default")
      (node (ref "U$2") (pin "15") (pinfunction "GPIO13_15") (pintype "bidirectional"))
    )
    (net (code "8") (name "/15") (class "Default")
      (node (ref "R31") (pin "1") (pinfunction "1_1") (pintype "passive"))
      (node (ref "U$2") (pin "2") (pinfunction "GPIO15_2") (pintype "bidirectional"))
    )
    (net (code "9") (name "/ADC") (class "Default")
      (node (ref "U$2") (pin "10") (pinfunction "ADC_10") (pintype "bidirectional"))
    )
    (net (code "10") (name "/BLUEMOSFET") (class "Default")
      (node (ref "D3") (pin "A") (pinfunction "A_A") (pintype "passive"))
      (node (ref "LED12") (pin "4") (pinfunction "BLUE_C_4") (pintype "bidirectional"))
      (node (ref "LED15") (pin "4") (pinfunction "BLUE_C_4") (pintype "bidirectional"))
      (node (ref "LED18") (pin "4") (pinfunction "BLUE_C_4") (pintype "bidirectional"))
      (node (ref "LED21") (pin "4") (pinfunction "BLUE_C_4") (pintype "bidirectional"))
      (node (ref "LED24") (pin "4") (pinfunction "BLUE_C_4") (pintype "bidirectional"))
      (node (ref "LED27") (pin "4") (pinfunction "BLUE_C_4") (pintype "bidirectional"))
      (node (ref "LED3") (pin "4") (pinfunction "BLUE_C_4") (pintype "bidirectional"))
      (node (ref "LED30") (pin "4") (pinfunction "BLUE_C_4") (pintype "bidirectional"))
      (node (ref "LED33") (pin "4") (pinfunction "BLUE_C_4") (pintype "bidirectional"))
      (node (ref "LED36") (pin "4") (pinfunction "BLUE_C_4") (pintype "bidirectional"))
      (node (ref "LED39") (pin "4") (pinfunction "BLUE_C_4") (pintype "bidirectional"))
      (node (ref "LED42") (pin "4") (pinfunction "BLUE_C_4") (pintype "bidirectional"))
      (node (ref "LED45") (pin "4") (pinfunction "BLUE_C_4") (pintype "bidirectional"))
      (node (ref "LED48") (pin "4") (pinfunction "BLUE_C_4") (pintype "bidirectional"))
      (node (ref "LED51") (pin "4") (pinfunction "BLUE_C_4") (pintype "bidirectional"))
      (node (ref "LED54") (pin "4") (pinfunction "BLUE_C_4") (pintype "bidirectional"))
      (node (ref "LED57") (pin "4") (pinfunction "BLUE_C_4") (pintype "bidirectional"))
      (node (ref "LED6") (pin "4") (pinfunction "BLUE_C_4") (pintype "bidirectional"))
      (node (ref "LED60") (pin "4") (pinfunction "BLUE_C_4") (pintype "bidirectional"))
      (node (ref "LED63") (pin "4") (pinfunction "BLUE_C_4") (pintype "bidirectional"))
      (node (ref "LED66") (pin "4") (pinfunction "BLUE_C_4") (pintype "bidirectional"))
      (node (ref "LED69") (pin "4") (pinfunction "BLUE_C_4") (pintype "bidirectional"))
      (node (ref "LED72") (pin "4") (pinfunction "BLUE_C_4") (pintype "bidirectional"))
      (node (ref "LED75") (pin "4") (pinfunction "BLUE_C_4") (pintype "bidirectional"))
      (node (ref "LED78") (pin "4") (pinfunction "BLUE_C_4") (pintype "bidirectional"))
      (node (ref "LED81") (pin "4") (pinfunction "BLUE_C_4") (pintype "bidirectional"))
      (node (ref "LED84") (pin "4") (pinfunction "BLUE_C_4") (pintype "bidirectional"))
      (node (ref "LED9") (pin "4") (pinfunction "BLUE_C_4") (pintype "bidirectional"))
      (node (ref "M3") (pin "3") (pinfunction "D_3") (pintype "passive"))
    )
    (net (code "11") (name "/BLUESIG") (class "Default")
      (node (ref "R5") (pin "1") (pinfunction "1_1") (pintype "passive"))
      (node (ref "U$2") (pin "14") (pinfunction "GPIO12_14") (pintype "bidirectional"))
    )
    (net (code "12") (name "/CHRX") (class "Default")
      (node (ref "U$2") (pin "8") (pinfunction "TXD_8") (pintype "bidirectional"))
    )
    (net (code "13") (name "/CHTX") (class "Default")
      (node (ref "U$2") (pin "7") (pinfunction "RXD_7") (pintype "bidirectional"))
    )
    (net (code "14") (name "/GREENMOSFET") (class "Default")
      (node (ref "D1") (pin "A") (pinfunction "A_A") (pintype "passive"))
      (node (ref "LED12") (pin "6") (pinfunction "GREEN_C_6") (pintype "bidirectional"))
      (node (ref "LED15") (pin "6") (pinfunction "GREEN_C_6") (pintype "bidirectional"))
      (node (ref "LED18") (pin "6") (pinfunction "GREEN_C_6") (pintype "bidirectional"))
      (node (ref "LED21") (pin "6") (pinfunction "GREEN_C_6") (pintype "bidirectional"))
      (node (ref "LED24") (pin "6") (pinfunction "GREEN_C_6") (pintype "bidirectional"))
      (node (ref "LED27") (pin "6") (pinfunction "GREEN_C_6") (pintype "bidirectional"))
      (node (ref "LED3") (pin "6") (pinfunction "GREEN_C_6") (pintype "bidirectional"))
      (node (ref "LED30") (pin "6") (pinfunction "GREEN_C_6") (pintype "bidirectional"))
      (node (ref "LED33") (pin "6") (pinfunction "GREEN_C_6") (pintype "bidirectional"))
      (node (ref "LED36") (pin "6") (pinfunction "GREEN_C_6") (pintype "bidirectional"))
      (node (ref "LED39") (pin "6") (pinfunction "GREEN_C_6") (pintype "bidirectional"))
      (node (ref "LED42") (pin "6") (pinfunction "GREEN_C_6") (pintype "bidirectional"))
      (node (ref "LED45") (pin "6") (pinfunction "GREEN_C_6") (pintype "bidirectional"))
      (node (ref "LED48") (pin "6") (pinfunction "GREEN_C_6") (pintype "bidirectional"))
      (node (ref "LED51") (pin "6") (pinfunction "GREEN_C_6") (pintype "bidirectional"))
      (node (ref "LED54") (pin "6") (pinfunction "GREEN_C_6") (pintype "bidirectional"))
      (node (ref "LED57") (pin "6") (pinfunction "GREEN_C_6") (pintype "bidirectional"))
      (node (ref "LED6") (pin "6") (pinfunction "GREEN_C_6") (pintype "bidirectional"))
      (node (ref "LED60") (pin "6") (pinfunction "GREEN_C_6") (pintype "bidirectional"))
      (node (ref "LED63") (pin "6") (pinfunction "GREEN_C_6") (pintype "bidirectional"))
      (node (ref "LED66") (pin "6") (pinfunction "GREEN_C_6") (pintype "bidirectional"))
      (node (ref "LED69") (pin "6") (pinfunction "GREEN_C_6") (pintype "bidirectional"))
      (node (ref "LED72") (pin "6") (pinfunction "GREEN_C_6") (pintype "bidirectional"))
      (node (ref "LED75") (pin "6") (pinfunction "GREEN_C_6") (pintype "bidirectional"))
      (node (ref "LED78") (pin "6") (pinfunction "GREEN_C_6") (pintype "bidirectional"))
      (node (ref "LED81") (pin "6") (pinfunction "GREEN_C_6") (pintype "bidirectional"))
      (node (ref "LED84") (pin "6") (pinfunction "GREEN_C_6") (pintype "bidirectional"))
      (node (ref "LED9") (pin "6") (pinfunction "GREEN_C_6") (pintype "bidirectional"))
      (node (ref "M2") (pin "3") (pinfunction "D_3") (pintype "passive"))
    )
    (net (code "15") (name "/GREENSIG") (class "Default")
      (node (ref "R3") (pin "1") (pinfunction "1_1") (pintype "passive"))
      (node (ref "U$2") (pin "13") (pinfunction "GPIO14_13") (pintype "bidirectional"))
    )
    (net (code "16") (name "/REDMOSFET") (class "Default")
      (node (ref "D10") (pin "A") (pinfunction "A_A") (pintype "passive"))
      (node (ref "LED12") (pin "5") (pinfunction "RED_C_5") (pintype "bidirectional"))
      (node (ref "LED15") (pin "5") (pinfunction "RED_C_5") (pintype "bidirectional"))
      (node (ref "LED18") (pin "5") (pinfunction "RED_C_5") (pintype "bidirectional"))
      (node (ref "LED21") (pin "5") (pinfunction "RED_C_5") (pintype "bidirectional"))
      (node (ref "LED24") (pin "5") (pinfunction "RED_C_5") (pintype "bidirectional"))
      (node (ref "LED27") (pin "5") (pinfunction "RED_C_5") (pintype "bidirectional"))
      (node (ref "LED3") (pin "5") (pinfunction "RED_C_5") (pintype "bidirectional"))
      (node (ref "LED30") (pin "5") (pinfunction "RED_C_5") (pintype "bidirectional"))
      (node (ref "LED33") (pin "5") (pinfunction "RED_C_5") (pintype "bidirectional"))
      (node (ref "LED36") (pin "5") (pinfunction "RED_C_5") (pintype "bidirectional"))
      (node (ref "LED39") (pin "5") (pinfunction "RED_C_5") (pintype "bidirectional"))
      (node (ref "LED42") (pin "5") (pinfunction "RED_C_5") (pintype "bidirectional"))
      (node (ref "LED45") (pin "5") (pinfunction "RED_C_5") (pintype "bidirectional"))
      (node (ref "LED48") (pin "5") (pinfunction "RED_C_5") (pintype "bidirectional"))
      (node (ref "LED51") (pin "5") (pinfunction "RED_C_5") (pintype "bidirectional"))
      (node (ref "LED54") (pin "5") (pinfunction "RED_C_5") (pintype "bidirectional"))
      (node (ref "LED57") (pin "5") (pinfunction "RED_C_5") (pintype "bidirectional"))
      (node (ref "LED6") (pin "5") (pinfunction "RED_C_5") (pintype "bidirectional"))
      (node (ref "LED60") (pin "5") (pinfunction "RED_C_5") (pintype "bidirectional"))
      (node (ref "LED63") (pin "5") (pinfunction "RED_C_5") (pintype "bidirectional"))
      (node (ref "LED66") (pin "5") (pinfunction "RED_C_5") (pintype "bidirectional"))
      (node (ref "LED69") (pin "5") (pinfunction "RED_C_5") (pintype "bidirectional"))
      (node (ref "LED72") (pin "5") (pinfunction "RED_C_5") (pintype "bidirectional"))
      (node (ref "LED75") (pin "5") (pinfunction "RED_C_5") (pintype "bidirectional"))
      (node (ref "LED78") (pin "5") (pinfunction "RED_C_5") (pintype "bidirectional"))
      (node (ref "LED81") (pin "5") (pinfunction "RED_C_5") (pintype "bidirectional"))
      (node (ref "LED84") (pin "5") (pinfunction "RED_C_5") (pintype "bidirectional"))
      (node (ref "LED9") (pin "5") (pinfunction "RED_C_5") (pintype "bidirectional"))
      (node (ref "M1") (pin "3") (pinfunction "D_3") (pintype "passive"))
    )
    (net (code "17") (name "/REDSIG") (class "Default")
      (node (ref "R11") (pin "1") (pinfunction "1_1") (pintype "passive"))
      (node (ref "U$2") (pin "12") (pinfunction "GPIO16_12") (pintype "bidirectional"))
    )
    (net (code "18") (name "/RESET") (class "Default")
      (node (ref "R29") (pin "2") (pinfunction "2_2") (pintype "passive"))
      (node (ref "S1") (pin "1") (pinfunction "1_1") (pintype "passive"))
      (node (ref "S1") (pin "2") (pinfunction "2_2") (pintype "passive"))
      (node (ref "U$2") (pin "9") (pinfunction "REST_9") (pintype "bidirectional"))
    )
    (net (code "19") (name "/VM") (class "Default")
      (node (ref "C26") (pin "+") (pinfunction "+_+") (pintype "passive"))
      (node (ref "D1") (pin "C") (pinfunction "C_C") (pintype "passive"))
      (node (ref "D10") (pin "C") (pinfunction "C_C") (pintype "passive"))
      (node (ref "D3") (pin "C") (pinfunction "C_C") (pintype "passive"))
      (node (ref "R10") (pin "1") (pinfunction "1_1") (pintype "passive"))
      (node (ref "R12") (pin "1") (pinfunction "1_1") (pintype "passive"))
      (node (ref "R13") (pin "1") (pinfunction "1_1") (pintype "passive"))
      (node (ref "R14") (pin "1") (pinfunction "1_1") (pintype "passive"))
      (node (ref "R16") (pin "1") (pinfunction "1_1") (pintype "passive"))
      (node (ref "R17") (pin "1") (pinfunction "1_1") (pintype "passive"))
      (node (ref "R18") (pin "1") (pinfunction "1_1") (pintype "passive"))
      (node (ref "R19") (pin "1") (pinfunction "1_1") (pintype "passive"))
      (node (ref "R20") (pin "1") (pinfunction "1_1") (pintype "passive"))
      (node (ref "R21") (pin "1") (pinfunction "1_1") (pintype "passive"))
      (node (ref "R22") (pin "1") (pinfunction "1_1") (pintype "passive"))
      (node (ref "R23") (pin "1") (pinfunction "1_1") (pintype "passive"))
      (node (ref "R24") (pin "1") (pinfunction "1_1") (pintype "passive"))
      (node (ref "R25") (pin "1") (pinfunction "1_1") (pintype "passive"))
      (node (ref "R26") (pin "1") (pinfunction "1_1") (pintype "passive"))
      (node (ref "R27") (pin "1") (pinfunction "1_1") (pintype "passive"))
      (node (ref "R30") (pin "1") (pinfunction "1_1") (pintype "passive"))
      (node (ref "R32") (pin "1") (pinfunction "1_1") (pintype "passive"))
      (node (ref "R33") (pin "1") (pinfunction "1_1") (pintype "passive"))
      (node (ref "R34") (pin "1") (pinfunction "1_1") (pintype "passive"))
      (node (ref "R35") (pin "1") (pinfunction "1_1") (pintype "passive"))
      (node (ref "R36") (pin "1") (pinfunction "1_1") (pintype "passive"))
      (node (ref "R37") (pin "1") (pinfunction "1_1") (pintype "passive"))
      (node (ref "R38") (pin "1") (pinfunction "1_1") (pintype "passive"))
      (node (ref "R39") (pin "1") (pinfunction "1_1") (pintype "passive"))
      (node (ref "R40") (pin "1") (pinfunction "1_1") (pintype "passive"))
      (node (ref "R41") (pin "1") (pinfunction "1_1") (pintype "passive"))
      (node (ref "R42") (pin "1") (pinfunction "1_1") (pintype "passive"))
      (node (ref "R43") (pin "1") (pinfunction "1_1") (pintype "passive"))
      (node (ref "R44") (pin "1") (pinfunction "1_1") (pintype "passive"))
      (node (ref "R45") (pin "1") (pinfunction "1_1") (pintype "passive"))
      (node (ref "R46") (pin "1") (pinfunction "1_1") (pintype "passive"))
      (node (ref "R47") (pin "1") (pinfunction "1_1") (pintype "passive"))
      (node (ref "R48") (pin "1") (pinfunction "1_1") (pintype "passive"))
      (node (ref "R49") (pin "1") (pinfunction "1_1") (pintype "passive"))
      (node (ref "R50") (pin "1") (pinfunction "1_1") (pintype "passive"))
      (node (ref "R51") (pin "1") (pinfunction "1_1") (pintype "passive"))
      (node (ref "R52") (pin "1") (pinfunction "1_1") (pintype "passive"))
      (node (ref "R53") (pin "1") (pinfunction "1_1") (pintype "passive"))
      (node (ref "R54") (pin "1") (pinfunction "1_1") (pintype "passive"))
      (node (ref "R55") (pin "1") (pinfunction "1_1") (pintype "passive"))
      (node (ref "R56") (pin "1") (pinfunction "1_1") (pintype "passive"))
      (node (ref "R57") (pin "1") (pinfunction "1_1") (pintype "passive"))
      (node (ref "R58") (pin "1") (pinfunction "1_1") (pintype "passive"))
      (node (ref "R59") (pin "1") (pinfunction "1_1") (pintype "passive"))
      (node (ref "R60") (pin "1") (pinfunction "1_1") (pintype "passive"))
      (node (ref "R61") (pin "1") (pinfunction "1_1") (pintype "passive"))
      (node (ref "R62") (pin "1") (pinfunction "1_1") (pintype "passive"))
      (node (ref "R63") (pin "1") (pinfunction "1_1") (pintype "passive"))
      (node (ref "R64") (pin "1") (pinfunction "1_1") (pintype "passive"))
      (node (ref "R65") (pin "1") (pinfunction "1_1") (pintype "passive"))
      (node (ref "R66") (pin "1") (pinfunction "1_1") (pintype "passive"))
      (node (ref "R67") (pin "1") (pinfunction "1_1") (pintype "passive"))
      (node (ref "R68") (pin "1") (pinfunction "1_1") (pintype "passive"))
      (node (ref "R69") (pin "1") (pinfunction "1_1") (pintype "passive"))
      (node (ref "R7") (pin "1") (pinfunction "1_1") (pintype "passive"))
      (node (ref "R70") (pin "1") (pinfunction "1_1") (pintype "passive"))
      (node (ref "R71") (pin "1") (pinfunction "1_1") (pintype "passive"))
      (node (ref "R72") (pin "1") (pinfunction "1_1") (pintype "passive"))
      (node (ref "R73") (pin "1") (pinfunction "1_1") (pintype "passive"))
      (node (ref "R74") (pin "1") (pinfunction "1_1") (pintype "passive"))
      (node (ref "R75") (pin "1") (pinfunction "1_1") (pintype "passive"))
      (node (ref "R76") (pin "1") (pinfunction "1_1") (pintype "passive"))
      (node (ref "R77") (pin "1") (pinfunction "1_1") (pintype "passive"))
      (node (ref "R78") (pin "1") (pinfunction "1_1") (pintype "passive"))
      (node (ref "R79") (pin "1") (pinfunction "1_1") (pintype "passive"))
      (node (ref "R8") (pin "1") (pinfunction "1_1") (pintype "passive"))
      (node (ref "R80") (pin "1") (pinfunction "1_1") (pintype "passive"))
      (node (ref "R81") (pin "1") (pinfunction "1_1") (pintype "passive"))
      (node (ref "R82") (pin "1") (pinfunction "1_1") (pintype "passive"))
      (node (ref "R83") (pin "1") (pinfunction "1_1") (pintype "passive"))
      (node (ref "R84") (pin "1") (pinfunction "1_1") (pintype "passive"))
      (node (ref "R85") (pin "1") (pinfunction "1_1") (pintype "passive"))
      (node (ref "R86") (pin "1") (pinfunction "1_1") (pintype "passive"))
      (node (ref "R87") (pin "1") (pinfunction "1_1") (pintype "passive"))
      (node (ref "R88") (pin "1") (pinfunction "1_1") (pintype "passive"))
      (node (ref "R89") (pin "1") (pinfunction "1_1") (pintype "passive"))
      (node (ref "R9") (pin "1") (pinfunction "1_1") (pintype "passive"))
      (node (ref "R90") (pin "1") (pinfunction "1_1") (pintype "passive"))
      (node (ref "R91") (pin "1") (pinfunction "1_1") (pintype "passive"))
      (node (ref "R92") (pin "1") (pinfunction "1_1") (pintype "passive"))
      (node (ref "R93") (pin "1") (pinfunction "1_1") (pintype "passive"))
      (node (ref "R94") (pin "1") (pinfunction "1_1") (pintype "passive"))
      (node (ref "R95") (pin "1") (pinfunction "1_1") (pintype "passive"))
      (node (ref "U$1") (pin "1") (pinfunction "IN_1") (pintype "bidirectional"))
    )
    (net (code "20") (name "GND") (class "Default")
      (node (ref "C13") (pin "-") (pinfunction "-_-") (pintype "passive"))
      (node (ref "C15") (pin "-") (pinfunction "-_-") (pintype "passive"))
      (node (ref "C26") (pin "-") (pinfunction "-_-") (pintype "passive"))
      (node (ref "D2") (pin "2") (pinfunction "A_2") (pintype "passive"))
      (node (ref "IC5") (pin "1") (pinfunction "ADJ_1") (pintype "input"))
      (node (ref "M1") (pin "2") (pinfunction "S_2") (pintype "passive"))
      (node (ref "M2") (pin "2") (pinfunction "S_2") (pintype "passive"))
      (node (ref "M3") (pin "2") (pinfunction "S_2") (pintype "passive"))
      (node (ref "R15") (pin "2") (pinfunction "2_2") (pintype "passive"))
      (node (ref "R31") (pin "2") (pinfunction "2_2") (pintype "passive"))
      (node (ref "R4") (pin "2") (pinfunction "2_2") (pintype "passive"))
      (node (ref "R6") (pin "2") (pinfunction "2_2") (pintype "passive"))
      (node (ref "S1") (pin "3") (pinfunction "3_3") (pintype "passive"))
      (node (ref "S1") (pin "4") (pinfunction "4_4") (pintype "passive"))
      (node (ref "U$1") (pin "4") (pinfunction "EN_4") (pintype "bidirectional"))
      (node (ref "U$1") (pin "5") (pinfunction "GND1_5") (pintype "bidirectional"))
      (node (ref "U$1") (pin "6") (pinfunction "GND2_6") (pintype "bidirectional"))
      (node (ref "U$1") (pin "7") (pinfunction "GND3_7") (pintype "bidirectional"))
      (node (ref "U$1") (pin "8") (pinfunction "GND4_8") (pintype "bidirectional"))
      (node (ref "U$2") (pin "1") (pinfunction "GND_1") (pintype "bidirectional"))
    )
    (net (code "21") (name "Net-(D2-C)") (class "Default")
      (node (ref "D2") (pin "1") (pinfunction "C_1") (pintype "passive"))
      (node (ref "L5") (pin "2") (pinfunction "2_2") (pintype "passive"))
      (node (ref "U$1") (pin "2") (pinfunction "OUT_2") (pintype "bidirectional"))
    )
    (net (code "22") (name "Net-(LED1-BLUE_A)") (class "Default")
      (node (ref "LED1") (pin "3") (pinfunction "BLUE_A_3") (pintype "bidirectional"))
      (node (ref "R7") (pin "2") (pinfunction "2_2") (pintype "passive"))
    )
    (net (code "23") (name "Net-(LED1-BLUE_C)") (class "Default")
      (node (ref "LED1") (pin "4") (pinfunction "BLUE_C_4") (pintype "bidirectional"))
      (node (ref "LED2") (pin "3") (pinfunction "BLUE_A_3") (pintype "bidirectional"))
    )
    (net (code "24") (name "Net-(LED1-GREEN_A)") (class "Default")
      (node (ref "LED1") (pin "1") (pinfunction "GREEN_A_1") (pintype "bidirectional"))
      (node (ref "R8") (pin "2") (pinfunction "2_2") (pintype "passive"))
    )
    (net (code "25") (name "Net-(LED1-GREEN_C)") (class "Default")
      (node (ref "LED1") (pin "6") (pinfunction "GREEN_C_6") (pintype "bidirectional"))
      (node (ref "LED2") (pin "1") (pinfunction "GREEN_A_1") (pintype "bidirectional"))
    )
    (net (code "26") (name "Net-(LED1-RED_A)") (class "Default")
      (node (ref "LED1") (pin "2") (pinfunction "RED_A_2") (pintype "bidirectional"))
      (node (ref "R9") (pin "2") (pinfunction "2_2") (pintype "passive"))
    )
    (net (code "27") (name "Net-(LED1-RED_C)") (class "Default")
      (node (ref "LED1") (pin "5") (pinfunction "RED_C_5") (pintype "bidirectional"))
      (node (ref "LED2") (pin "2") (pinfunction "RED_A_2") (pintype "bidirectional"))
    )
    (net (code "28") (name "Net-(LED2-BLUE_C)") (class "Default")
      (node (ref "LED2") (pin "4") (pinfunction "BLUE_C_4") (pintype "bidirectional"))
      (node (ref "LED3") (pin "3") (pinfunction "BLUE_A_3") (pintype "bidirectional"))
    )
    (net (code "29") (name "Net-(LED2-GREEN_C)") (class "Default")
      (node (ref "LED2") (pin "6") (pinfunction "GREEN_C_6") (pintype "bidirectional"))
      (node (ref "LED3") (pin "1") (pinfunction "GREEN_A_1") (pintype "bidirectional"))
    )
    (net (code "30") (name "Net-(LED2-RED_C)") (class "Default")
      (node (ref "LED2") (pin "5") (pinfunction "RED_C_5") (pintype "bidirectional"))
      (node (ref "LED3") (pin "2") (pinfunction "RED_A_2") (pintype "bidirectional"))
    )
    (net (code "31") (name "Net-(LED4-BLUE_A)") (class "Default")
      (node (ref "LED4") (pin "3") (pinfunction "BLUE_A_3") (pintype "bidirectional"))
      (node (ref "R10") (pin "2") (pinfunction "2_2") (pintype "passive"))
    )
    (net (code "32") (name "Net-(LED4-BLUE_C)") (class "Default")
      (node (ref "LED4") (pin "4") (pinfunction "BLUE_C_4") (pintype "bidirectional"))
      (node (ref "LED5") (pin "3") (pinfunction "BLUE_A_3") (pintype "bidirectional"))
    )
    (net (code "33") (name "Net-(LED4-GREEN_A)") (class "Default")
      (node (ref "LED4") (pin "1") (pinfunction "GREEN_A_1") (pintype "bidirectional"))
      (node (ref "R12") (pin "2") (pinfunction "2_2") (pintype "passive"))
    )
    (net (code "34") (name "Net-(LED4-GREEN_C)") (class "Default")
      (node (ref "LED4") (pin "6") (pinfunction "GREEN_C_6") (pintype "bidirectional"))
      (node (ref "LED5") (pin "1") (pinfunction "GREEN_A_1") (pintype "bidirectional"))
    )
    (net (code "35") (name "Net-(LED4-RED_A)") (class "Default")
      (node (ref "LED4") (pin "2") (pinfunction "RED_A_2") (pintype "bidirectional"))
      (node (ref "R13") (pin "2") (pinfunction "2_2") (pintype "passive"))
    )
    (net (code "36") (name "Net-(LED4-RED_C)") (class "Default")
      (node (ref "LED4") (pin "5") (pinfunction "RED_C_5") (pintype "bidirectional"))
      (node (ref "LED5") (pin "2") (pinfunction "RED_A_2") (pintype "bidirectional"))
    )
    (net (code "37") (name "Net-(LED5-BLUE_C)") (class "Default")
      (node (ref "LED5") (pin "4") (pinfunction "BLUE_C_4") (pintype "bidirectional"))
      (node (ref "LED6") (pin "3") (pinfunction "BLUE_A_3") (pintype "bidirectional"))
    )
    (net (code "38") (name "Net-(LED5-GREEN_C)") (class "Default")
      (node (ref "LED5") (pin "6") (pinfunction "GREEN_C_6") (pintype "bidirectional"))
      (node (ref "LED6") (pin "1") (pinfunction "GREEN_A_1") (pintype "bidirectional"))
    )
    (net (code "39") (name "Net-(LED5-RED_C)") (class "Default")
      (node (ref "LED5") (pin "5") (pinfunction "RED_C_5") (pintype "bidirectional"))
      (node (ref "LED6") (pin "2") (pinfunction "RED_A_2") (pintype "bidirectional"))
    )
    (net (code "40") (name "Net-(LED7-BLUE_A)") (class "Default")
      (node (ref "LED7") (pin "3") (pinfunction "BLUE_A_3") (pintype "bidirectional"))
      (node (ref "R17") (pin "2") (pinfunction "2_2") (pintype "passive"))
    )
    (net (code "41") (name "Net-(LED7-BLUE_C)") (class "Default")
      (node (ref "LED7") (pin "4") (pinfunction "BLUE_C_4") (pintype "bidirectional"))
      (node (ref "LED8") (pin "3") (pinfunction "BLUE_A_3") (pintype "bidirectional"))
    )
    (net (code "42") (name "Net-(LED7-GREEN_A)") (class "Default")
      (node (ref "LED7") (pin "1") (pinfunction "GREEN_A_1") (pintype "bidirectional"))
      (node (ref "R16") (pin "2") (pinfunction "2_2") (pintype "passive"))
    )
    (net (code "43") (name "Net-(LED7-GREEN_C)") (class "Default")
      (node (ref "LED7") (pin "6") (pinfunction "GREEN_C_6") (pintype "bidirectional"))
      (node (ref "LED8") (pin "1") (pinfunction "GREEN_A_1") (pintype "bidirectional"))
    )
    (net (code "44") (name "Net-(LED7-RED_A)") (class "Default")
      (node (ref "LED7") (pin "2") (pinfunction "RED_A_2") (pintype "bidirectional"))
      (node (ref "R14") (pin "2") (pinfunction "2_2") (pintype "passive"))
    )
    (net (code "45") (name "Net-(LED7-RED_C)") (class "Default")
      (node (ref "LED7") (pin "5") (pinfunction "RED_C_5") (pintype "bidirectional"))
      (node (ref "LED8") (pin "2") (pinfunction "RED_A_2") (pintype "bidirectional"))
    )
    (net (code "46") (name "Net-(LED8-BLUE_C)") (class "Default")
      (node (ref "LED8") (pin "4") (pinfunction "BLUE_C_4") (pintype "bidirectional"))
      (node (ref "LED9") (pin "3") (pinfunction "BLUE_A_3") (pintype "bidirectional"))
    )
    (net (code "47") (name "Net-(LED8-GREEN_C)") (class "Default")
      (node (ref "LED8") (pin "6") (pinfunction "GREEN_C_6") (pintype "bidirectional"))
      (node (ref "LED9") (pin "1") (pinfunction "GREEN_A_1") (pintype "bidirectional"))
    )
    (net (code "48") (name "Net-(LED8-RED_C)") (class "Default")
      (node (ref "LED8") (pin "5") (pinfunction "RED_C_5") (pintype "bidirectional"))
      (node (ref "LED9") (pin "2") (pinfunction "RED_A_2") (pintype "bidirectional"))
    )
    (net (code "49") (name "Net-(LED10-BLUE_A)") (class "Default")
      (node (ref "LED10") (pin "3") (pinfunction "BLUE_A_3") (pintype "bidirectional"))
      (node (ref "R20") (pin "2") (pinfunction "2_2") (pintype "passive"))
    )
    (net (code "50") (name "Net-(LED10-BLUE_C)") (class "Default")
      (node (ref "LED10") (pin "4") (pinfunction "BLUE_C_4") (pintype "bidirectional"))
      (node (ref "LED11") (pin "3") (pinfunction "BLUE_A_3") (pintype "bidirectional"))
    )
    (net (code "51") (name "Net-(LED10-GREEN_A)") (class "Default")
      (node (ref "LED10") (pin "1") (pinfunction "GREEN_A_1") (pintype "bidirectional"))
      (node (ref "R19") (pin "2") (pinfunction "2_2") (pintype "passive"))
    )
    (net (code "52") (name "Net-(LED10-GREEN_C)") (class "Default")
      (node (ref "LED10") (pin "6") (pinfunction "GREEN_C_6") (pintype "bidirectional"))
      (node (ref "LED11") (pin "1") (pinfunction "GREEN_A_1") (pintype "bidirectional"))
    )
    (net (code "53") (name "Net-(LED10-RED_A)") (class "Default")
      (node (ref "LED10") (pin "2") (pinfunction "RED_A_2") (pintype "bidirectional"))
      (node (ref "R18") (pin "2") (pinfunction "2_2") (pintype "passive"))
    )
    (net (code "54") (name "Net-(LED10-RED_C)") (class "Default")
      (node (ref "LED10") (pin "5") (pinfunction "RED_C_5") (pintype "bidirectional"))
      (node (ref "LED11") (pin "2") (pinfunction "RED_A_2") (pintype "bidirectional"))
    )
    (net (code "55") (name "Net-(LED11-BLUE_C)") (class "Default")
      (node (ref "LED11") (pin "4") (pinfunction "BLUE_C_4") (pintype "bidirectional"))
      (node (ref "LED12") (pin "3") (pinfunction "BLUE_A_3") (pintype "bidirectional"))
    )
    (net (code "56") (name "Net-(LED11-GREEN_C)") (class "Default")
      (node (ref "LED11") (pin "6") (pinfunction "GREEN_C_6") (pintype "bidirectional"))
      (node (ref "LED12") (pin "1") (pinfunction "GREEN_A_1") (pintype "bidirectional"))
    )
    (net (code "57") (name "Net-(LED11-RED_C)") (class "Default")
      (node (ref "LED11") (pin "5") (pinfunction "RED_C_5") (pintype "bidirectional"))
      (node (ref "LED12") (pin "2") (pinfunction "RED_A_2") (pintype "bidirectional"))
    )
    (net (code "58") (name "Net-(LED13-BLUE_A)") (class "Default")
      (node (ref "LED13") (pin "3") (pinfunction "BLUE_A_3") (pintype "bidirectional"))
      (node (ref "R36") (pin "2") (pinfunction "2_2") (pintype "passive"))
    )
    (net (code "59") (name "Net-(LED13-BLUE_C)") (class "Default")
      (node (ref "LED13") (pin "4") (pinfunction "BLUE_C_4") (pintype "bidirectional"))
      (node (ref "LED14") (pin "3") (pinfunction "BLUE_A_3") (pintype "bidirectional"))
    )
    (net (code "60") (name "Net-(LED13-GREEN_A)") (class "Default")
      (node (ref "LED13") (pin "1") (pinfunction "GREEN_A_1") (pintype "bidirectional"))
      (node (ref "R37") (pin "2") (pinfunction "2_2") (pintype "passive"))
    )
    (net (code "61") (name "Net-(LED13-GREEN_C)") (class "Default")
      (node (ref "LED13") (pin "6") (pinfunction "GREEN_C_6") (pintype "bidirectional"))
      (node (ref "LED14") (pin "1") (pinfunction "GREEN_A_1") (pintype "bidirectional"))
    )
    (net (code "62") (name "Net-(LED13-RED_A)") (class "Default")
      (node (ref "LED13") (pin "2") (pinfunction "RED_A_2") (pintype "bidirectional"))
      (node (ref "R38") (pin "2") (pinfunction "2_2") (pintype "passive"))
    )
    (net (code "63") (name "Net-(LED13-RED_C)") (class "Default")
      (node (ref "LED13") (pin "5") (pinfunction "RED_C_5") (pintype "bidirectional"))
      (node (ref "LED14") (pin "2") (pinfunction "RED_A_2") (pintype "bidirectional"))
    )
    (net (code "64") (name "Net-(LED14-BLUE_C)") (class "Default")
      (node (ref "LED14") (pin "4") (pinfunction "BLUE_C_4") (pintype "bidirectional"))
      (node (ref "LED15") (pin "3") (pinfunction "BLUE_A_3") (pintype "bidirectional"))
    )
    (net (code "65") (name "Net-(LED14-GREEN_C)") (class "Default")
      (node (ref "LED14") (pin "6") (pinfunction "GREEN_C_6") (pintype "bidirectional"))
      (node (ref "LED15") (pin "1") (pinfunction "GREEN_A_1") (pintype "bidirectional"))
    )
    (net (code "66") (name "Net-(LED14-RED_C)") (class "Default")
      (node (ref "LED14") (pin "5") (pinfunction "RED_C_5") (pintype "bidirectional"))
      (node (ref "LED15") (pin "2") (pinfunction "RED_A_2") (pintype "bidirectional"))
    )
    (net (code "67") (name "Net-(LED16-BLUE_A)") (class "Default")
      (node (ref "LED16") (pin "3") (pinfunction "BLUE_A_3") (pintype "bidirectional"))
      (node (ref "R39") (pin "2") (pinfunction "2_2") (pintype "passive"))
    )
    (net (code "68") (name "Net-(LED16-BLUE_C)") (class "Default")
      (node (ref "LED16") (pin "4") (pinfunction "BLUE_C_4") (pintype "bidirectional"))
      (node (ref "LED17") (pin "3") (pinfunction "BLUE_A_3") (pintype "bidirectional"))
    )
    (net (code "69") (name "Net-(LED16-GREEN_A)") (class "Default")
      (node (ref "LED16") (pin "1") (pinfunction "GREEN_A_1") (pintype "bidirectional"))
      (node (ref "R40") (pin "2") (pinfunction "2_2") (pintype "passive"))
    )
    (net (code "70") (name "Net-(LED16-GREEN_C)") (class "Default")
      (node (ref "LED16") (pin "6") (pinfunction "GREEN_C_6") (pintype "bidirectional"))
      (node (ref "LED17") (pin "1") (pinfunction "GREEN_A_1") (pintype "bidirectional"))
    )
    (net (code "71") (name "Net-(LED16-RED_A)") (class "Default")
      (node (ref "LED16") (pin "2") (pinfunction "RED_A_2") (pintype "bidirectional"))
      (node (ref "R41") (pin "2") (pinfunction "2_2") (pintype "passive"))
    )
    (net (code "72") (name "Net-(LED16-RED_C)") (class "Default")
      (node (ref "LED16") (pin "5") (pinfunction "RED_C_5") (pintype "bidirectional"))
      (node (ref "LED17") (pin "2") (pinfunction "RED_A_2") (pintype "bidirectional"))
    )
    (net (code "73") (name "Net-(LED17-BLUE_C)") (class "Default")
      (node (ref "LED17") (pin "4") (pinfunction "BLUE_C_4") (pintype "bidirectional"))
      (node (ref "LED18") (pin "3") (pinfunction "BLUE_A_3") (pintype "bidirectional"))
    )
    (net (code "74") (name "Net-(LED17-GREEN_C)") (class "Default")
      (node (ref "LED17") (pin "6") (pinfunction "GREEN_C_6") (pintype "bidirectional"))
      (node (ref "LED18") (pin "1") (pinfunction "GREEN_A_1") (pintype "bidirectional"))
    )
    (net (code "75") (name "Net-(LED17-RED_C)") (class "Default")
      (node (ref "LED17") (pin "5") (pinfunction "RED_C_5") (pintype "bidirectional"))
      (node (ref "LED18") (pin "2") (pinfunction "RED_A_2") (pintype "bidirectional"))
    )
    (net (code "76") (name "Net-(LED19-BLUE_A)") (class "Default")
      (node (ref "LED19") (pin "3") (pinfunction "BLUE_A_3") (pintype "bidirectional"))
      (node (ref "R42") (pin "2") (pinfunction "2_2") (pintype "passive"))
    )
    (net (code "77") (name "Net-(LED19-BLUE_C)") (class "Default")
      (node (ref "LED19") (pin "4") (pinfunction "BLUE_C_4") (pintype "bidirectional"))
      (node (ref "LED20") (pin "3") (pinfunction "BLUE_A_3") (pintype "bidirectional"))
    )
    (net (code "78") (name "Net-(LED19-GREEN_A)") (class "Default")
      (node (ref "LED19") (pin "1") (pinfunction "GREEN_A_1") (pintype "bidirectional"))
      (node (ref "R43") (pin "2") (pinfunction "2_2") (pintype "passive"))
    )
    (net (code "79") (name "Net-(LED19-GREEN_C)") (class "Default")
      (node (ref "LED19") (pin "6") (pinfunction "GREEN_C_6") (pintype "bidirectional"))
      (node (ref "LED20") (pin "1") (pinfunction "GREEN_A_1") (pintype "bidirectional"))
    )
    (net (code "80") (name "Net-(LED19-RED_A)") (class "Default")
      (node (ref "LED19") (pin "2") (pinfunction "RED_A_2") (pintype "bidirectional"))
      (node (ref "R44") (pin "2") (pinfunction "2_2") (pintype "passive"))
    )
    (net (code "81") (name "Net-(LED19-RED_C)") (class "Default")
      (node (ref "LED19") (pin "5") (pinfunction "RED_C_5") (pintype "bidirectional"))
      (node (ref "LED20") (pin "2") (pinfunction "RED_A_2") (pintype "bidirectional"))
    )
    (net (code "82") (name "Net-(LED20-BLUE_C)") (class "Default")
      (node (ref "LED20") (pin "4") (pinfunction "BLUE_C_4") (pintype "bidirectional"))
      (node (ref "LED21") (pin "3") (pinfunction "BLUE_A_3") (pintype "bidirectional"))
    )
    (net (code "83") (name "Net-(LED20-GREEN_C)") (class "Default")
      (node (ref "LED20") (pin "6") (pinfunction "GREEN_C_6") (pintype "bidirectional"))
      (node (ref "LED21") (pin "1") (pinfunction "GREEN_A_1") (pintype "bidirectional"))
    )
    (net (code "84") (name "Net-(LED20-RED_C)") (class "Default")
      (node (ref "LED20") (pin "5") (pinfunction "RED_C_5") (pintype "bidirectional"))
      (node (ref "LED21") (pin "2") (pinfunction "RED_A_2") (pintype "bidirectional"))
    )
    (net (code "85") (name "Net-(LED22-BLUE_A)") (class "Default")
      (node (ref "LED22") (pin "3") (pinfunction "BLUE_A_3") (pintype "bidirectional"))
      (node (ref "R45") (pin "2") (pinfunction "2_2") (pintype "passive"))
    )
    (net (code "86") (name "Net-(LED22-BLUE_C)") (class "Default")
      (node (ref "LED22") (pin "4") (pinfunction "BLUE_C_4") (pintype "bidirectional"))
      (node (ref "LED23") (pin "3") (pinfunction "BLUE_A_3") (pintype "bidirectional"))
    )
    (net (code "87") (name "Net-(LED22-GREEN_A)") (class "Default")
      (node (ref "LED22") (pin "1") (pinfunction "GREEN_A_1") (pintype "bidirectional"))
      (node (ref "R46") (pin "2") (pinfunction "2_2") (pintype "passive"))
    )
    (net (code "88") (name "Net-(LED22-GREEN_C)") (class "Default")
      (node (ref "LED22") (pin "6") (pinfunction "GREEN_C_6") (pintype "bidirectional"))
      (node (ref "LED23") (pin "1") (pinfunction "GREEN_A_1") (pintype "bidirectional"))
    )
    (net (code "89") (name "Net-(LED22-RED_A)") (class "Default")
      (node (ref "LED22") (pin "2") (pinfunction "RED_A_2") (pintype "bidirectional"))
      (node (ref "R47") (pin "2") (pinfunction "2_2") (pintype "passive"))
    )
    (net (code "90") (name "Net-(LED22-RED_C)") (class "Default")
      (node (ref "LED22") (pin "5") (pinfunction "RED_C_5") (pintype "bidirectional"))
      (node (ref "LED23") (pin "2") (pinfunction "RED_A_2") (pintype "bidirectional"))
    )
    (net (code "91") (name "Net-(LED23-BLUE_C)") (class "Default")
      (node (ref "LED23") (pin "4") (pinfunction "BLUE_C_4") (pintype "bidirectional"))
      (node (ref "LED24") (pin "3") (pinfunction "BLUE_A_3") (pintype "bidirectional"))
    )
    (net (code "92") (name "Net-(LED23-GREEN_C)") (class "Default")
      (node (ref "LED23") (pin "6") (pinfunction "GREEN_C_6") (pintype "bidirectional"))
      (node (ref "LED24") (pin "1") (pinfunction "GREEN_A_1") (pintype "bidirectional"))
    )
    (net (code "93") (name "Net-(LED23-RED_C)") (class "Default")
      (node (ref "LED23") (pin "5") (pinfunction "RED_C_5") (pintype "bidirectional"))
      (node (ref "LED24") (pin "2") (pinfunction "RED_A_2") (pintype "bidirectional"))
    )
    (net (code "94") (name "Net-(LED25-BLUE_A)") (class "Default")
      (node (ref "LED25") (pin "3") (pinfunction "BLUE_A_3") (pintype "bidirectional"))
      (node (ref "R23") (pin "2") (pinfunction "2_2") (pintype "passive"))
    )
    (net (code "95") (name "Net-(LED25-BLUE_C)") (class "Default")
      (node (ref "LED25") (pin "4") (pinfunction "BLUE_C_4") (pintype "bidirectional"))
      (node (ref "LED26") (pin "3") (pinfunction "BLUE_A_3") (pintype "bidirectional"))
    )
    (net (code "96") (name "Net-(LED25-GREEN_A)") (class "Default")
      (node (ref "LED25") (pin "1") (pinfunction "GREEN_A_1") (pintype "bidirectional"))
      (node (ref "R22") (pin "2") (pinfunction "2_2") (pintype "passive"))
    )
    (net (code "97") (name "Net-(LED25-GREEN_C)") (class "Default")
      (node (ref "LED25") (pin "6") (pinfunction "GREEN_C_6") (pintype "bidirectional"))
      (node (ref "LED26") (pin "1") (pinfunction "GREEN_A_1") (pintype "bidirectional"))
    )
    (net (code "98") (name "Net-(LED25-RED_A)") (class "Default")
      (node (ref "LED25") (pin "2") (pinfunction "RED_A_2") (pintype "bidirectional"))
      (node (ref "R21") (pin "2") (pinfunction "2_2") (pintype "passive"))
    )
    (net (code "99") (name "Net-(LED25-RED_C)") (class "Default")
      (node (ref "LED25") (pin "5") (pinfunction "RED_C_5") (pintype "bidirectional"))
      (node (ref "LED26") (pin "2") (pinfunction "RED_A_2") (pintype "bidirectional"))
    )
    (net (code "100") (name "Net-(LED26-BLUE_C)") (class "Default")
      (node (ref "LED26") (pin "4") (pinfunction "BLUE_C_4") (pintype "bidirectional"))
      (node (ref "LED27") (pin "3") (pinfunction "BLUE_A_3") (pintype "bidirectional"))
    )
    (net (code "101") (name "Net-(LED26-GREEN_C)") (class "Default")
      (node (ref "LED26") (pin "6") (pinfunction "GREEN_C_6") (pintype "bidirectional"))
      (node (ref "LED27") (pin "1") (pinfunction "GREEN_A_1") (pintype "bidirectional"))
    )
    (net (code "102") (name "Net-(LED26-RED_C)") (class "Default")
      (node (ref "LED26") (pin "5") (pinfunction "RED_C_5") (pintype "bidirectional"))
      (node (ref "LED27") (pin "2") (pinfunction "RED_A_2") (pintype "bidirectional"))
    )
    (net (code "103") (name "Net-(LED28-BLUE_A)") (class "Default")
      (node (ref "LED28") (pin "3") (pinfunction "BLUE_A_3") (pintype "bidirectional"))
      (node (ref "R24") (pin "2") (pinfunction "2_2") (pintype "passive"))
    )
    (net (code "104") (name "Net-(LED28-BLUE_C)") (class "Default")
      (node (ref "LED28") (pin "4") (pinfunction "BLUE_C_4") (pintype "bidirectional"))
      (node (ref "LED29") (pin "3") (pinfunction "BLUE_A_3") (pintype "bidirectional"))
    )
    (net (code "105") (name "Net-(LED28-GREEN_A)") (class "Default")
      (node (ref "LED28") (pin "1") (pinfunction "GREEN_A_1") (pintype "bidirectional"))
      (node (ref "R25") (pin "2") (pinfunction "2_2") (pintype "passive"))
    )
    (net (code "106") (name "Net-(LED28-GREEN_C)") (class "Default")
      (node (ref "LED28") (pin "6") (pinfunction "GREEN_C_6") (pintype "bidirectional"))
      (node (ref "LED29") (pin "1") (pinfunction "GREEN_A_1") (pintype "bidirectional"))
    )
    (net (code "107") (name "Net-(LED28-RED_A)") (class "Default")
      (node (ref "LED28") (pin "2") (pinfunction "RED_A_2") (pintype "bidirectional"))
      (node (ref "R26") (pin "2") (pinfunction "2_2") (pintype "passive"))
    )
    (net (code "108") (name "Net-(LED28-RED_C)") (class "Default")
      (node (ref "LED28") (pin "5") (pinfunction "RED_C_5") (pintype "bidirectional"))
      (node (ref "LED29") (pin "2") (pinfunction "RED_A_2") (pintype "bidirectional"))
    )
    (net (code "109") (name "Net-(LED29-BLUE_C)") (class "Default")
      (node (ref "LED29") (pin "4") (pinfunction "BLUE_C_4") (pintype "bidirectional"))
      (node (ref "LED30") (pin "3") (pinfunction "BLUE_A_3") (pintype "bidirectional"))
    )
    (net (code "110") (name "Net-(LED29-GREEN_C)") (class "Default")
      (node (ref "LED29") (pin "6") (pinfunction "GREEN_C_6") (pintype "bidirectional"))
      (node (ref "LED30") (pin "1") (pinfunction "GREEN_A_1") (pintype "bidirectional"))
    )
    (net (code "111") (name "Net-(LED29-RED_C)") (class "Default")
      (node (ref "LED29") (pin "5") (pinfunction "RED_C_5") (pintype "bidirectional"))
      (node (ref "LED30") (pin "2") (pinfunction "RED_A_2") (pintype "bidirectional"))
    )
    (net (code "112") (name "Net-(LED31-BLUE_A)") (class "Default")
      (node (ref "LED31") (pin "3") (pinfunction "BLUE_A_3") (pintype "bidirectional"))
      (node (ref "R27") (pin "2") (pinfunction "2_2") (pintype "passive"))
    )
    (net (code "113") (name "Net-(LED31-BLUE_C)") (class "Default")
      (node (ref "LED31") (pin "4") (pinfunction "BLUE_C_4") (pintype "bidirectional"))
      (node (ref "LED32") (pin "3") (pinfunction "BLUE_A_3") (pintype "bidirectional"))
    )
    (net (code "114") (name "Net-(LED31-GREEN_A)") (class "Default")
      (node (ref "LED31") (pin "1") (pinfunction "GREEN_A_1") (pintype "bidirectional"))
      (node (ref "R30") (pin "2") (pinfunction "2_2") (pintype "passive"))
    )
    (net (code "115") (name "Net-(LED31-GREEN_C)") (class "Default")
      (node (ref "LED31") (pin "6") (pinfunction "GREEN_C_6") (pintype "bidirectional"))
      (node (ref "LED32") (pin "1") (pinfunction "GREEN_A_1") (pintype "bidirectional"))
    )
    (net (code "116") (name "Net-(LED31-RED_A)") (class "Default")
      (node (ref "LED31") (pin "2") (pinfunction "RED_A_2") (pintype "bidirectional"))
      (node (ref "R32") (pin "2") (pinfunction "2_2") (pintype "passive"))
    )
    (net (code "117") (name "Net-(LED31-RED_C)") (class "Default")
      (node (ref "LED31") (pin "5") (pinfunction "RED_C_5") (pintype "bidirectional"))
      (node (ref "LED32") (pin "2") (pinfunction "RED_A_2") (pintype "bidirectional"))
    )
    (net (code "118") (name "Net-(LED32-BLUE_C)") (class "Default")
      (node (ref "LED32") (pin "4") (pinfunction "BLUE_C_4") (pintype "bidirectional"))
      (node (ref "LED33") (pin "3") (pinfunction "BLUE_A_3") (pintype "bidirectional"))
    )
    (net (code "119") (name "Net-(LED32-GREEN_C)") (class "Default")
      (node (ref "LED32") (pin "6") (pinfunction "GREEN_C_6") (pintype "bidirectional"))
      (node (ref "LED33") (pin "1") (pinfunction "GREEN_A_1") (pintype "bidirectional"))
    )
    (net (code "120") (name "Net-(LED32-RED_C)") (class "Default")
      (node (ref "LED32") (pin "5") (pinfunction "RED_C_5") (pintype "bidirectional"))
      (node (ref "LED33") (pin "2") (pinfunction "RED_A_2") (pintype "bidirectional"))
    )
    (net (code "121") (name "Net-(LED34-BLUE_A)") (class "Default")
      (node (ref "LED34") (pin "3") (pinfunction "BLUE_A_3") (pintype "bidirectional"))
      (node (ref "R33") (pin "2") (pinfunction "2_2") (pintype "passive"))
    )
    (net (code "122") (name "Net-(LED34-BLUE_C)") (class "Default")
      (node (ref "LED34") (pin "4") (pinfunction "BLUE_C_4") (pintype "bidirectional"))
      (node (ref "LED35") (pin "3") (pinfunction "BLUE_A_3") (pintype "bidirectional"))
    )
    (net (code "123") (name "Net-(LED34-GREEN_A)") (class "Default")
      (node (ref "LED34") (pin "1") (pinfunction "GREEN_A_1") (pintype "bidirectional"))
      (node (ref "R34") (pin "2") (pinfunction "2_2") (pintype "passive"))
    )
    (net (code "124") (name "Net-(LED34-GREEN_C)") (class "Default")
      (node (ref "LED34") (pin "6") (pinfunction "GREEN_C_6") (pintype "bidirectional"))
      (node (ref "LED35") (pin "1") (pinfunction "GREEN_A_1") (pintype "bidirectional"))
    )
    (net (code "125") (name "Net-(LED34-RED_A)") (class "Default")
      (node (ref "LED34") (pin "2") (pinfunction "RED_A_2") (pintype "bidirectional"))
      (node (ref "R35") (pin "2") (pinfunction "2_2") (pintype "passive"))
    )
    (net (code "126") (name "Net-(LED34-RED_C)") (class "Default")
      (node (ref "LED34") (pin "5") (pinfunction "RED_C_5") (pintype "bidirectional"))
      (node (ref "LED35") (pin "2") (pinfunction "RED_A_2") (pintype "bidirectional"))
    )
    (net (code "127") (name "Net-(LED35-BLUE_C)") (class "Default")
      (node (ref "LED35") (pin "4") (pinfunction "BLUE_C_4") (pintype "bidirectional"))
      (node (ref "LED36") (pin "3") (pinfunction "BLUE_A_3") (pintype "bidirectional"))
    )
    (net (code "128") (name "Net-(LED35-GREEN_C)") (class "Default")
      (node (ref "LED35") (pin "6") (pinfunction "GREEN_C_6") (pintype "bidirectional"))
      (node (ref "LED36") (pin "1") (pinfunction "GREEN_A_1") (pintype "bidirectional"))
    )
    (net (code "129") (name "Net-(LED35-RED_C)") (class "Default")
      (node (ref "LED35") (pin "5") (pinfunction "RED_C_5") (pintype "bidirectional"))
      (node (ref "LED36") (pin "2") (pinfunction "RED_A_2") (pintype "bidirectional"))
    )
    (net (code "130") (name "Net-(LED37-BLUE_A)") (class "Default")
      (node (ref "LED37") (pin "3") (pinfunction "BLUE_A_3") (pintype "bidirectional"))
      (node (ref "R48") (pin "2") (pinfunction "2_2") (pintype "passive"))
    )
    (net (code "131") (name "Net-(LED37-BLUE_C)") (class "Default")
      (node (ref "LED37") (pin "4") (pinfunction "BLUE_C_4") (pintype "bidirectional"))
      (node (ref "LED38") (pin "3") (pinfunction "BLUE_A_3") (pintype "bidirectional"))
    )
    (net (code "132") (name "Net-(LED37-GREEN_A)") (class "Default")
      (node (ref "LED37") (pin "1") (pinfunction "GREEN_A_1") (pintype "bidirectional"))
      (node (ref "R49") (pin "2") (pinfunction "2_2") (pintype "passive"))
    )
    (net (code "133") (name "Net-(LED37-GREEN_C)") (class "Default")
      (node (ref "LED37") (pin "6") (pinfunction "GREEN_C_6") (pintype "bidirectional"))
      (node (ref "LED38") (pin "1") (pinfunction "GREEN_A_1") (pintype "bidirectional"))
    )
    (net (code "134") (name "Net-(LED37-RED_A)") (class "Default")
      (node (ref "LED37") (pin "2") (pinfunction "RED_A_2") (pintype "bidirectional"))
      (node (ref "R50") (pin "2") (pinfunction "2_2") (pintype "passive"))
    )
    (net (code "135") (name "Net-(LED37-RED_C)") (class "Default")
      (node (ref "LED37") (pin "5") (pinfunction "RED_C_5") (pintype "bidirectional"))
      (node (ref "LED38") (pin "2") (pinfunction "RED_A_2") (pintype "bidirectional"))
    )
    (net (code "136") (name "Net-(LED38-BLUE_C)") (class "Default")
      (node (ref "LED38") (pin "4") (pinfunction "BLUE_C_4") (pintype "bidirectional"))
      (node (ref "LED39") (pin "3") (pinfunction "BLUE_A_3") (pintype "bidirectional"))
    )
    (net (code "137") (name "Net-(LED38-GREEN_C)") (class "Default")
      (node (ref "LED38") (pin "6") (pinfunction "GREEN_C_6") (pintype "bidirectional"))
      (node (ref "LED39") (pin "1") (pinfunction "GREEN_A_1") (pintype "bidirectional"))
    )
    (net (code "138") (name "Net-(LED38-RED_C)") (class "Default")
      (node (ref "LED38") (pin "5") (pinfunction "RED_C_5") (pintype "bidirectional"))
      (node (ref "LED39") (pin "2") (pinfunction "RED_A_2") (pintype "bidirectional"))
    )
    (net (code "139") (name "Net-(LED40-BLUE_A)") (class "Default")
      (node (ref "LED40") (pin "3") (pinfunction "BLUE_A_3") (pintype "bidirectional"))
      (node (ref "R51") (pin "2") (pinfunction "2_2") (pintype "passive"))
    )
    (net (code "140") (name "Net-(LED40-BLUE_C)") (class "Default")
      (node (ref "LED40") (pin "4") (pinfunction "BLUE_C_4") (pintype "bidirectional"))
      (node (ref "LED41") (pin "3") (pinfunction "BLUE_A_3") (pintype "bidirectional"))
    )
    (net (code "141") (name "Net-(LED40-GREEN_A)") (class "Default")
      (node (ref "LED40") (pin "1") (pinfunction "GREEN_A_1") (pintype "bidirectional"))
      (node (ref "R52") (pin "2") (pinfunction "2_2") (pintype "passive"))
    )
    (net (code "142") (name "Net-(LED40-GREEN_C)") (class "Default")
      (node (ref "LED40") (pin "6") (pinfunction "GREEN_C_6") (pintype "bidirectional"))
      (node (ref "LED41") (pin "1") (pinfunction "GREEN_A_1") (pintype "bidirectional"))
    )
    (net (code "143") (name "Net-(LED40-RED_A)") (class "Default")
      (node (ref "LED40") (pin "2") (pinfunction "RED_A_2") (pintype "bidirectional"))
      (node (ref "R53") (pin "2") (pinfunction "2_2") (pintype "passive"))
    )
    (net (code "144") (name "Net-(LED40-RED_C)") (class "Default")
      (node (ref "LED40") (pin "5") (pinfunction "RED_C_5") (pintype "bidirectional"))
      (node (ref "LED41") (pin "2") (pinfunction "RED_A_2") (pintype "bidirectional"))
    )
    (net (code "145") (name "Net-(LED41-BLUE_C)") (class "Default")
      (node (ref "LED41") (pin "4") (pinfunction "BLUE_C_4") (pintype "bidirectional"))
      (node (ref "LED42") (pin "3") (pinfunction "BLUE_A_3") (pintype "bidirectional"))
    )
    (net (code "146") (name "Net-(LED41-GREEN_C)") (class "Default")
      (node (ref "LED41") (pin "6") (pinfunction "GREEN_C_6") (pintype "bidirectional"))
      (node (ref "LED42") (pin "1") (pinfunction "GREEN_A_1") (pintype "bidirectional"))
    )
    (net (code "147") (name "Net-(LED41-RED_C)") (class "Default")
      (node (ref "LED41") (pin "5") (pinfunction "RED_C_5") (pintype "bidirectional"))
      (node (ref "LED42") (pin "2") (pinfunction "RED_A_2") (pintype "bidirectional"))
    )
    (net (code "148") (name "Net-(LED43-BLUE_A)") (class "Default")
      (node (ref "LED43") (pin "3") (pinfunction "BLUE_A_3") (pintype "bidirectional"))
      (node (ref "R54") (pin "2") (pinfunction "2_2") (pintype "passive"))
    )
    (net (code "149") (name "Net-(LED43-BLUE_C)") (class "Default")
      (node (ref "LED43") (pin "4") (pinfunction "BLUE_C_4") (pintype "bidirectional"))
      (node (ref "LED44") (pin "3") (pinfunction "BLUE_A_3") (pintype "bidirectional"))
    )
    (net (code "150") (name "Net-(LED43-GREEN_A)") (class "Default")
      (node (ref "LED43") (pin "1") (pinfunction "GREEN_A_1") (pintype "bidirectional"))
      (node (ref "R55") (pin "2") (pinfunction "2_2") (pintype "passive"))
    )
    (net (code "151") (name "Net-(LED43-GREEN_C)") (class "Default")
      (node (ref "LED43") (pin "6") (pinfunction "GREEN_C_6") (pintype "bidirectional"))
      (node (ref "LED44") (pin "1") (pinfunction "GREEN_A_1") (pintype "bidirectional"))
    )
    (net (code "152") (name "Net-(LED43-RED_A)") (class "Default")
      (node (ref "LED43") (pin "2") (pinfunction "RED_A_2") (pintype "bidirectional"))
      (node (ref "R56") (pin "2") (pinfunction "2_2") (pintype "passive"))
    )
    (net (code "153") (name "Net-(LED43-RED_C)") (class "Default")
      (node (ref "LED43") (pin "5") (pinfunction "RED_C_5") (pintype "bidirectional"))
      (node (ref "LED44") (pin "2") (pinfunction "RED_A_2") (pintype "bidirectional"))
    )
    (net (code "154") (name "Net-(LED44-BLUE_C)") (class "Default")
      (node (ref "LED44") (pin "4") (pinfunction "BLUE_C_4") (pintype "bidirectional"))
      (node (ref "LED45") (pin "3") (pinfunction "BLUE_A_3") (pintype "bidirectional"))
    )
    (net (code "155") (name "Net-(LED44-GREEN_C)") (class "Default")
      (node (ref "LED44") (pin "6") (pinfunction "GREEN_C_6") (pintype "bidirectional"))
      (node (ref "LED45") (pin "1") (pinfunction "GREEN_A_1") (pintype "bidirectional"))
    )
    (net (code "156") (name "Net-(LED44-RED_C)") (class "Default")
      (node (ref "LED44") (pin "5") (pinfunction "RED_C_5") (pintype "bidirectional"))
      (node (ref "LED45") (pin "2") (pinfunction "RED_A_2") (pintype "bidirectional"))
    )
    (net (code "157") (name "Net-(LED46-BLUE_A)") (class "Default")
      (node (ref "LED46") (pin "3") (pinfunction "BLUE_A_3") (pintype "bidirectional"))
      (node (ref "R57") (pin "2") (pinfunction "2_2") (pintype "passive"))
    )
    (net (code "158") (name "Net-(LED46-BLUE_C)") (class "Default")
      (node (ref "LED46") (pin "4") (pinfunction "BLUE_C_4") (pintype "bidirectional"))
      (node (ref "LED47") (pin "3") (pinfunction "BLUE_A_3") (pintype "bidirectional"))
    )
    (net (code "159") (name "Net-(LED46-GREEN_A)") (class "Default")
      (node (ref "LED46") (pin "1") (pinfunction "GREEN_A_1") (pintype "bidirectional"))
      (node (ref "R58") (pin "2") (pinfunction "2_2") (pintype "passive"))
    )
    (net (code "160") (name "Net-(LED46-GREEN_C)") (class "Default")
      (node (ref "LED46") (pin "6") (pinfunction "GREEN_C_6") (pintype "bidirectional"))
      (node (ref "LED47") (pin "1") (pinfunction "GREEN_A_1") (pintype "bidirectional"))
    )
    (net (code "161") (name "Net-(LED46-RED_A)") (class "Default")
      (node (ref "LED46") (pin "2") (pinfunction "RED_A_2") (pintype "bidirectional"))
      (node (ref "R59") (pin "2") (pinfunction "2_2") (pintype "passive"))
    )
    (net (code "162") (name "Net-(LED46-RED_C)") (class "Default")
      (node (ref "LED46") (pin "5") (pinfunction "RED_C_5") (pintype "bidirectional"))
      (node (ref "LED47") (pin "2") (pinfunction "RED_A_2") (pintype "bidirectional"))
    )
    (net (code "163") (name "Net-(LED47-BLUE_C)") (class "Default")
      (node (ref "LED47") (pin "4") (pinfunction "BLUE_C_4") (pintype "bidirectional"))
      (node (ref "LED48") (pin "3") (pinfunction "BLUE_A_3") (pintype "bidirectional"))
    )
    (net (code "164") (name "Net-(LED47-GREEN_C)") (class "Default")
      (node (ref "LED47") (pin "6") (pinfunction "GREEN_C_6") (pintype "bidirectional"))
      (node (ref "LED48") (pin "1") (pinfunction "GREEN_A_1") (pintype "bidirectional"))
    )
    (net (code "165") (name "Net-(LED47-RED_C)") (class "Default")
      (node (ref "LED47") (pin "5") (pinfunction "RED_C_5") (pintype "bidirectional"))
      (node (ref "LED48") (pin "2") (pinfunction "RED_A_2") (pintype "bidirectional"))
    )
    (net (code "166") (name "Net-(LED49-BLUE_A)") (class "Default")
      (node (ref "LED49") (pin "3") (pinfunction "BLUE_A_3") (pintype "bidirectional"))
      (node (ref "R60") (pin "2") (pinfunction "2_2") (pintype "passive"))
    )
    (net (code "167") (name "Net-(LED49-BLUE_C)") (class "Default")
      (node (ref "LED49") (pin "4") (pinfunction "BLUE_C_4") (pintype "bidirectional"))
      (node (ref "LED50") (pin "3") (pinfunction "BLUE_A_3") (pintype "bidirectional"))
    )
    (net (code "168") (name "Net-(LED49-GREEN_A)") (class "Default")
      (node (ref "LED49") (pin "1") (pinfunction "GREEN_A_1") (pintype "bidirectional"))
      (node (ref "R61") (pin "2") (pinfunction "2_2") (pintype "passive"))
    )
    (net (code "169") (name "Net-(LED49-GREEN_C)") (class "Default")
      (node (ref "LED49") (pin "6") (pinfunction "GREEN_C_6") (pintype "bidirectional"))
      (node (ref "LED50") (pin "1") (pinfunction "GREEN_A_1") (pintype "bidirectional"))
    )
    (net (code "170") (name "Net-(LED49-RED_A)") (class "Default")
      (node (ref "LED49") (pin "2") (pinfunction "RED_A_2") (pintype "bidirectional"))
      (node (ref "R62") (pin "2") (pinfunction "2_2") (pintype "passive"))
    )
    (net (code "171") (name "Net-(LED49-RED_C)") (class "Default")
      (node (ref "LED49") (pin "5") (pinfunction "RED_C_5") (pintype "bidirectional"))
      (node (ref "LED50") (pin "2") (pinfunction "RED_A_2") (pintype "bidirectional"))
    )
    (net (code "172") (name "Net-(LED50-BLUE_C)") (class "Default")
      (node (ref "LED50") (pin "4") (pinfunction "BLUE_C_4") (pintype "bidirectional"))
      (node (ref "LED51") (pin "3") (pinfunction "BLUE_A_3") (pintype "bidirectional"))
    )
    (net (code "173") (name "Net-(LED50-GREEN_C)") (class "Default")
      (node (ref "LED50") (pin "6") (pinfunction "GREEN_C_6") (pintype "bidirectional"))
      (node (ref "LED51") (pin "1") (pinfunction "GREEN_A_1") (pintype "bidirectional"))
    )
    (net (code "174") (name "Net-(LED50-RED_C)") (class "Default")
      (node (ref "LED50") (pin "5") (pinfunction "RED_C_5") (pintype "bidirectional"))
      (node (ref "LED51") (pin "2") (pinfunction "RED_A_2") (pintype "bidirectional"))
    )
    (net (code "175") (name "Net-(LED52-BLUE_A)") (class "Default")
      (node (ref "LED52") (pin "3") (pinfunction "BLUE_A_3") (pintype "bidirectional"))
      (node (ref "R63") (pin "2") (pinfunction "2_2") (pintype "passive"))
    )
    (net (code "176") (name "Net-(LED52-BLUE_C)") (class "Default")
      (node (ref "LED52") (pin "4") (pinfunction "BLUE_C_4") (pintype "bidirectional"))
      (node (ref "LED53") (pin "3") (pinfunction "BLUE_A_3") (pintype "bidirectional"))
    )
    (net (code "177") (name "Net-(LED52-GREEN_A)") (class "Default")
      (node (ref "LED52") (pin "1") (pinfunction "GREEN_A_1") (pintype "bidirectional"))
      (node (ref "R64") (pin "2") (pinfunction "2_2") (pintype "passive"))
    )
    (net (code "178") (name "Net-(LED52-GREEN_C)") (class "Default")
      (node (ref "LED52") (pin "6") (pinfunction "GREEN_C_6") (pintype "bidirectional"))
      (node (ref "LED53") (pin "1") (pinfunction "GREEN_A_1") (pintype "bidirectional"))
    )
    (net (code "179") (name "Net-(LED52-RED_A)") (class "Default")
      (node (ref "LED52") (pin "2") (pinfunction "RED_A_2") (pintype "bidirectional"))
      (node (ref "R65") (pin "2") (pinfunction "2_2") (pintype "passive"))
    )
    (net (code "180") (name "Net-(LED52-RED_C)") (class "Default")
      (node (ref "LED52") (pin "5") (pinfunction "RED_C_5") (pintype "bidirectional"))
      (node (ref "LED53") (pin "2") (pinfunction "RED_A_2") (pintype "bidirectional"))
    )
    (net (code "181") (name "Net-(LED53-BLUE_C)") (class "Default")
      (node (ref "LED53") (pin "4") (pinfunction "BLUE_C_4") (pintype "bidirectional"))
      (node (ref "LED54") (pin "3") (pinfunction "BLUE_A_3") (pintype "bidirectional"))
    )
    (net (code "182") (name "Net-(LED53-GREEN_C)") (class "Default")
      (node (ref "LED53") (pin "6") (pinfunction "GREEN_C_6") (pintype "bidirectional"))
      (node (ref "LED54") (pin "1") (pinfunction "GREEN_A_1") (pintype "bidirectional"))
    )
    (net (code "183") (name "Net-(LED53-RED_C)") (class "Default")
      (node (ref "LED53") (pin "5") (pinfunction "RED_C_5") (pintype "bidirectional"))
      (node (ref "LED54") (pin "2") (pinfunction "RED_A_2") (pintype "bidirectional"))
    )
    (net (code "184") (name "Net-(LED55-BLUE_A)") (class "Default")
      (node (ref "LED55") (pin "3") (pinfunction "BLUE_A_3") (pintype "bidirectional"))
      (node (ref "R66") (pin "2") (pinfunction "2_2") (pintype "passive"))
    )
    (net (code "185") (name "Net-(LED55-BLUE_C)") (class "Default")
      (node (ref "LED55") (pin "4") (pinfunction "BLUE_C_4") (pintype "bidirectional"))
      (node (ref "LED56") (pin "3") (pinfunction "BLUE_A_3") (pintype "bidirectional"))
    )
    (net (code "186") (name "Net-(LED55-GREEN_A)") (class "Default")
      (node (ref "LED55") (pin "1") (pinfunction "GREEN_A_1") (pintype "bidirectional"))
      (node (ref "R67") (pin "2") (pinfunction "2_2") (pintype "passive"))
    )
    (net (code "187") (name "Net-(LED55-GREEN_C)") (class "Default")
      (node (ref "LED55") (pin "6") (pinfunction "GREEN_C_6") (pintype "bidirectional"))
      (node (ref "LED56") (pin "1") (pinfunction "GREEN_A_1") (pintype "bidirectional"))
    )
    (net (code "188") (name "Net-(LED55-RED_A)") (class "Default")
      (node (ref "LED55") (pin "2") (pinfunction "RED_A_2") (pintype "bidirectional"))
      (node (ref "R68") (pin "2") (pinfunction "2_2") (pintype "passive"))
    )
    (net (code "189") (name "Net-(LED55-RED_C)") (class "Default")
      (node (ref "LED55") (pin "5") (pinfunction "RED_C_5") (pintype "bidirectional"))
      (node (ref "LED56") (pin "2") (pinfunction "RED_A_2") (pintype "bidirectional"))
    )
    (net (code "190") (name "Net-(LED56-BLUE_C)") (class "Default")
      (node (ref "LED56") (pin "4") (pinfunction "BLUE_C_4") (pintype "bidirectional"))
      (node (ref "LED57") (pin "3") (pinfunction "BLUE_A_3") (pintype "bidirectional"))
    )
    (net (code "191") (name "Net-(LED56-GREEN_C)") (class "Default")
      (node (ref "LED56") (pin "6") (pinfunction "GREEN_C_6") (pintype "bidirectional"))
      (node (ref "LED57") (pin "1") (pinfunction "GREEN_A_1") (pintype "bidirectional"))
    )
    (net (code "192") (name "Net-(LED56-RED_C)") (class "Default")
      (node (ref "LED56") (pin "5") (pinfunction "RED_C_5") (pintype "bidirectional"))
      (node (ref "LED57") (pin "2") (pinfunction "RED_A_2") (pintype "bidirectional"))
    )
    (net (code "193") (name "Net-(LED58-BLUE_A)") (class "Default")
      (node (ref "LED58") (pin "3") (pinfunction "BLUE_A_3") (pintype "bidirectional"))
      (node (ref "R69") (pin "2") (pinfunction "2_2") (pintype "passive"))
    )
    (net (code "194") (name "Net-(LED58-BLUE_C)") (class "Default")
      (node (ref "LED58") (pin "4") (pinfunction "BLUE_C_4") (pintype "bidirectional"))
      (node (ref "LED59") (pin "3") (pinfunction "BLUE_A_3") (pintype "bidirectional"))
    )
    (net (code "195") (name "Net-(LED58-GREEN_A)") (class "Default")
      (node (ref "LED58") (pin "1") (pinfunction "GREEN_A_1") (pintype "bidirectional"))
      (node (ref "R70") (pin "2") (pinfunction "2_2") (pintype "passive"))
    )
    (net (code "196") (name "Net-(LED58-GREEN_C)") (class "Default")
      (node (ref "LED58") (pin "6") (pinfunction "GREEN_C_6") (pintype "bidirectional"))
      (node (ref "LED59") (pin "1") (pinfunction "GREEN_A_1") (pintype "bidirectional"))
    )
    (net (code "197") (name "Net-(LED58-RED_A)") (class "Default")
      (node (ref "LED58") (pin "2") (pinfunction "RED_A_2") (pintype "bidirectional"))
      (node (ref "R71") (pin "2") (pinfunction "2_2") (pintype "passive"))
    )
    (net (code "198") (name "Net-(LED58-RED_C)") (class "Default")
      (node (ref "LED58") (pin "5") (pinfunction "RED_C_5") (pintype "bidirectional"))
      (node (ref "LED59") (pin "2") (pinfunction "RED_A_2") (pintype "bidirectional"))
    )
    (net (code "199") (name "Net-(LED59-BLUE_C)") (class "Default")
      (node (ref "LED59") (pin "4") (pinfunction "BLUE_C_4") (pintype "bidirectional"))
      (node (ref "LED60") (pin "3") (pinfunction "BLUE_A_3") (pintype "bidirectional"))
    )
    (net (code "200") (name "Net-(LED59-GREEN_C)") (class "Default")
      (node (ref "LED59") (pin "6") (pinfunction "GREEN_C_6") (pintype "bidirectional"))
      (node (ref "LED60") (pin "1") (pinfunction "GREEN_A_1") (pintype "bidirectional"))
    )
    (net (code "201") (name "Net-(LED59-RED_C)") (class "Default")
      (node (ref "LED59") (pin "5") (pinfunction "RED_C_5") (pintype "bidirectional"))
      (node (ref "LED60") (pin "2") (pinfunction "RED_A_2") (pintype "bidirectional"))
    )
    (net (code "202") (name "Net-(LED61-BLUE_A)") (class "Default")
      (node (ref "LED61") (pin "3") (pinfunction "BLUE_A_3") (pintype "bidirectional"))
      (node (ref "R84") (pin "2") (pinfunction "2_2") (pintype "passive"))
    )
    (net (code "203") (name "Net-(LED61-BLUE_C)") (class "Default")
      (node (ref "LED61") (pin "4") (pinfunction "BLUE_C_4") (pintype "bidirectional"))
      (node (ref "LED62") (pin "3") (pinfunction "BLUE_A_3") (pintype "bidirectional"))
    )
    (net (code "204") (name "Net-(LED61-GREEN_A)") (class "Default")
      (node (ref "LED61") (pin "1") (pinfunction "GREEN_A_1") (pintype "bidirectional"))
      (node (ref "R85") (pin "2") (pinfunction "2_2") (pintype "passive"))
    )
    (net (code "205") (name "Net-(LED61-GREEN_C)") (class "Default")
      (node (ref "LED61") (pin "6") (pinfunction "GREEN_C_6") (pintype "bidirectional"))
      (node (ref "LED62") (pin "1") (pinfunction "GREEN_A_1") (pintype "bidirectional"))
    )
    (net (code "206") (name "Net-(LED61-RED_A)") (class "Default")
      (node (ref "LED61") (pin "2") (pinfunction "RED_A_2") (pintype "bidirectional"))
      (node (ref "R86") (pin "2") (pinfunction "2_2") (pintype "passive"))
    )
    (net (code "207") (name "Net-(LED61-RED_C)") (class "Default")
      (node (ref "LED61") (pin "5") (pinfunction "RED_C_5") (pintype "bidirectional"))
      (node (ref "LED62") (pin "2") (pinfunction "RED_A_2") (pintype "bidirectional"))
    )
    (net (code "208") (name "Net-(LED62-BLUE_C)") (class "Default")
      (node (ref "LED62") (pin "4") (pinfunction "BLUE_C_4") (pintype "bidirectional"))
      (node (ref "LED63") (pin "3") (pinfunction "BLUE_A_3") (pintype "bidirectional"))
    )
    (net (code "209") (name "Net-(LED62-GREEN_C)") (class "Default")
      (node (ref "LED62") (pin "6") (pinfunction "GREEN_C_6") (pintype "bidirectional"))
      (node (ref "LED63") (pin "1") (pinfunction "GREEN_A_1") (pintype "bidirectional"))
    )
    (net (code "210") (name "Net-(LED62-RED_C)") (class "Default")
      (node (ref "LED62") (pin "5") (pinfunction "RED_C_5") (pintype "bidirectional"))
      (node (ref "LED63") (pin "2") (pinfunction "RED_A_2") (pintype "bidirectional"))
    )
    (net (code "211") (name "Net-(LED64-BLUE_A)") (class "Default")
      (node (ref "LED64") (pin "3") (pinfunction "BLUE_A_3") (pintype "bidirectional"))
      (node (ref "R87") (pin "2") (pinfunction "2_2") (pintype "passive"))
    )
    (net (code "212") (name "Net-(LED64-BLUE_C)") (class "Default")
      (node (ref "LED64") (pin "4") (pinfunction "BLUE_C_4") (pintype "bidirectional"))
      (node (ref "LED65") (pin "3") (pinfunction "BLUE_A_3") (pintype "bidirectional"))
    )
    (net (code "213") (name "Net-(LED64-GREEN_A)") (class "Default")
      (node (ref "LED64") (pin "1") (pinfunction "GREEN_A_1") (pintype "bidirectional"))
      (node (ref "R88") (pin "2") (pinfunction "2_2") (pintype "passive"))
    )
    (net (code "214") (name "Net-(LED64-GREEN_C)") (class "Default")
      (node (ref "LED64") (pin "6") (pinfunction "GREEN_C_6") (pintype "bidirectional"))
      (node (ref "LED65") (pin "1") (pinfunction "GREEN_A_1") (pintype "bidirectional"))
    )
    (net (code "215") (name "Net-(LED64-RED_A)") (class "Default")
      (node (ref "LED64") (pin "2") (pinfunction "RED_A_2") (pintype "bidirectional"))
      (node (ref "R89") (pin "2") (pinfunction "2_2") (pintype "passive"))
    )
    (net (code "216") (name "Net-(LED64-RED_C)") (class "Default")
      (node (ref "LED64") (pin "5") (pinfunction "RED_C_5") (pintype "bidirectional"))
      (node (ref "LED65") (pin "2") (pinfunction "RED_A_2") (pintype "bidirectional"))
    )
    (net (code "217") (name "Net-(LED65-BLUE_C)") (class "Default")
      (node (ref "LED65") (pin "4") (pinfunction "BLUE_C_4") (pintype "bidirectional"))
      (node (ref "LED66") (pin "3") (pinfunction "BLUE_A_3") (pintype "bidirectional"))
    )
    (net (code "218") (name "Net-(LED65-GREEN_C)") (class "Default")
      (node (ref "LED65") (pin "6") (pinfunction "GREEN_C_6") (pintype "bidirectional"))
      (node (ref "LED66") (pin "1") (pinfunction "GREEN_A_1") (pintype "bidirectional"))
    )
    (net (code "219") (name "Net-(LED65-RED_C)") (class "Default")
      (node (ref "LED65") (pin "5") (pinfunction "RED_C_5") (pintype "bidirectional"))
      (node (ref "LED66") (pin "2") (pinfunction "RED_A_2") (pintype "bidirectional"))
    )
    (net (code "220") (name "Net-(LED67-BLUE_A)") (class "Default")
      (node (ref "LED67") (pin "3") (pinfunction "BLUE_A_3") (pintype "bidirectional"))
      (node (ref "R90") (pin "2") (pinfunction "2_2") (pintype "passive"))
    )
    (net (code "221") (name "Net-(LED67-BLUE_C)") (class "Default")
      (node (ref "LED67") (pin "4") (pinfunction "BLUE_C_4") (pintype "bidirectional"))
      (node (ref "LED68") (pin "3") (pinfunction "BLUE_A_3") (pintype "bidirectional"))
    )
    (net (code "222") (name "Net-(LED67-GREEN_A)") (class "Default")
      (node (ref "LED67") (pin "1") (pinfunction "GREEN_A_1") (pintype "bidirectional"))
      (node (ref "R91") (pin "2") (pinfunction "2_2") (pintype "passive"))
    )
    (net (code "223") (name "Net-(LED67-GREEN_C)") (class "Default")
      (node (ref "LED67") (pin "6") (pinfunction "GREEN_C_6") (pintype "bidirectional"))
      (node (ref "LED68") (pin "1") (pinfunction "GREEN_A_1") (pintype "bidirectional"))
    )
    (net (code "224") (name "Net-(LED67-RED_A)") (class "Default")
      (node (ref "LED67") (pin "2") (pinfunction "RED_A_2") (pintype "bidirectional"))
      (node (ref "R92") (pin "2") (pinfunction "2_2") (pintype "passive"))
    )
    (net (code "225") (name "Net-(LED67-RED_C)") (class "Default")
      (node (ref "LED67") (pin "5") (pinfunction "RED_C_5") (pintype "bidirectional"))
      (node (ref "LED68") (pin "2") (pinfunction "RED_A_2") (pintype "bidirectional"))
    )
    (net (code "226") (name "Net-(LED68-BLUE_C)") (class "Default")
      (node (ref "LED68") (pin "4") (pinfunction "BLUE_C_4") (pintype "bidirectional"))
      (node (ref "LED69") (pin "3") (pinfunction "BLUE_A_3") (pintype "bidirectional"))
    )
    (net (code "227") (name "Net-(LED68-GREEN_C)") (class "Default")
      (node (ref "LED68") (pin "6") (pinfunction "GREEN_C_6") (pintype "bidirectional"))
      (node (ref "LED69") (pin "1") (pinfunction "GREEN_A_1") (pintype "bidirectional"))
    )
    (net (code "228") (name "Net-(LED68-RED_C)") (class "Default")
      (node (ref "LED68") (pin "5") (pinfunction "RED_C_5") (pintype "bidirectional"))
      (node (ref "LED69") (pin "2") (pinfunction "RED_A_2") (pintype "bidirectional"))
    )
    (net (code "229") (name "Net-(LED70-BLUE_A)") (class "Default")
      (node (ref "LED70") (pin "3") (pinfunction "BLUE_A_3") (pintype "bidirectional"))
      (node (ref "R93") (pin "2") (pinfunction "2_2") (pintype "passive"))
    )
    (net (code "230") (name "Net-(LED70-BLUE_C)") (class "Default")
      (node (ref "LED70") (pin "4") (pinfunction "BLUE_C_4") (pintype "bidirectional"))
      (node (ref "LED71") (pin "3") (pinfunction "BLUE_A_3") (pintype "bidirectional"))
    )
    (net (code "231") (name "Net-(LED70-GREEN_A)") (class "Default")
      (node (ref "LED70") (pin "1") (pinfunction "GREEN_A_1") (pintype "bidirectional"))
      (node (ref "R94") (pin "2") (pinfunction "2_2") (pintype "passive"))
    )
    (net (code "232") (name "Net-(LED70-GREEN_C)") (class "Default")
      (node (ref "LED70") (pin "6") (pinfunction "GREEN_C_6") (pintype "bidirectional"))
      (node (ref "LED71") (pin "1") (pinfunction "GREEN_A_1") (pintype "bidirectional"))
    )
    (net (code "233") (name "Net-(LED70-RED_A)") (class "Default")
      (node (ref "LED70") (pin "2") (pinfunction "RED_A_2") (pintype "bidirectional"))
      (node (ref "R95") (pin "2") (pinfunction "2_2") (pintype "passive"))
    )
    (net (code "234") (name "Net-(LED70-RED_C)") (class "Default")
      (node (ref "LED70") (pin "5") (pinfunction "RED_C_5") (pintype "bidirectional"))
      (node (ref "LED71") (pin "2") (pinfunction "RED_A_2") (pintype "bidirectional"))
    )
    (net (code "235") (name "Net-(LED71-BLUE_C)") (class "Default")
      (node (ref "LED71") (pin "4") (pinfunction "BLUE_C_4") (pintype "bidirectional"))
      (node (ref "LED72") (pin "3") (pinfunction "BLUE_A_3") (pintype "bidirectional"))
    )
    (net (code "236") (name "Net-(LED71-GREEN_C)") (class "Default")
      (node (ref "LED71") (pin "6") (pinfunction "GREEN_C_6") (pintype "bidirectional"))
      (node (ref "LED72") (pin "1") (pinfunction "GREEN_A_1") (pintype "bidirectional"))
    )
    (net (code "237") (name "Net-(LED71-RED_C)") (class "Default")
      (node (ref "LED71") (pin "5") (pinfunction "RED_C_5") (pintype "bidirectional"))
      (node (ref "LED72") (pin "2") (pinfunction "RED_A_2") (pintype "bidirectional"))
    )
    (net (code "238") (name "Net-(LED73-BLUE_A)") (class "Default")
      (node (ref "LED73") (pin "3") (pinfunction "BLUE_A_3") (pintype "bidirectional"))
      (node (ref "R72") (pin "2") (pinfunction "2_2") (pintype "passive"))
    )
    (net (code "239") (name "Net-(LED73-BLUE_C)") (class "Default")
      (node (ref "LED73") (pin "4") (pinfunction "BLUE_C_4") (pintype "bidirectional"))
      (node (ref "LED74") (pin "3") (pinfunction "BLUE_A_3") (pintype "bidirectional"))
    )
    (net (code "240") (name "Net-(LED73-GREEN_A)") (class "Default")
      (node (ref "LED73") (pin "1") (pinfunction "GREEN_A_1") (pintype "bidirectional"))
      (node (ref "R73") (pin "2") (pinfunction "2_2") (pintype "passive"))
    )
    (net (code "241") (name "Net-(LED73-GREEN_C)") (class "Default")
      (node (ref "LED73") (pin "6") (pinfunction "GREEN_C_6") (pintype "bidirectional"))
      (node (ref "LED74") (pin "1") (pinfunction "GREEN_A_1") (pintype "bidirectional"))
    )
    (net (code "242") (name "Net-(LED73-RED_A)") (class "Default")
      (node (ref "LED73") (pin "2") (pinfunction "RED_A_2") (pintype "bidirectional"))
      (node (ref "R74") (pin "2") (pinfunction "2_2") (pintype "passive"))
    )
    (net (code "243") (name "Net-(LED73-RED_C)") (class "Default")
      (node (ref "LED73") (pin "5") (pinfunction "RED_C_5") (pintype "bidirectional"))
      (node (ref "LED74") (pin "2") (pinfunction "RED_A_2") (pintype "bidirectional"))
    )
    (net (code "244") (name "Net-(LED74-BLUE_C)") (class "Default")
      (node (ref "LED74") (pin "4") (pinfunction "BLUE_C_4") (pintype "bidirectional"))
      (node (ref "LED75") (pin "3") (pinfunction "BLUE_A_3") (pintype "bidirectional"))
    )
    (net (code "245") (name "Net-(LED74-GREEN_C)") (class "Default")
      (node (ref "LED74") (pin "6") (pinfunction "GREEN_C_6") (pintype "bidirectional"))
      (node (ref "LED75") (pin "1") (pinfunction "GREEN_A_1") (pintype "bidirectional"))
    )
    (net (code "246") (name "Net-(LED74-RED_C)") (class "Default")
      (node (ref "LED74") (pin "5") (pinfunction "RED_C_5") (pintype "bidirectional"))
      (node (ref "LED75") (pin "2") (pinfunction "RED_A_2") (pintype "bidirectional"))
    )
    (net (code "247") (name "Net-(LED76-BLUE_A)") (class "Default")
      (node (ref "LED76") (pin "3") (pinfunction "BLUE_A_3") (pintype "bidirectional"))
      (node (ref "R75") (pin "2") (pinfunction "2_2") (pintype "passive"))
    )
    (net (code "248") (name "Net-(LED76-BLUE_C)") (class "Default")
      (node (ref "LED76") (pin "4") (pinfunction "BLUE_C_4") (pintype "bidirectional"))
      (node (ref "LED77") (pin "3") (pinfunction "BLUE_A_3") (pintype "bidirectional"))
    )
    (net (code "249") (name "Net-(LED76-GREEN_A)") (class "Default")
      (node (ref "LED76") (pin "1") (pinfunction "GREEN_A_1") (pintype "bidirectional"))
      (node (ref "R76") (pin "2") (pinfunction "2_2") (pintype "passive"))
    )
    (net (code "250") (name "Net-(LED76-GREEN_C)") (class "Default")
      (node (ref "LED76") (pin "6") (pinfunction "GREEN_C_6") (pintype "bidirectional"))
      (node (ref "LED77") (pin "1") (pinfunction "GREEN_A_1") (pintype "bidirectional"))
    )
    (net (code "251") (name "Net-(LED76-RED_A)") (class "Default")
      (node (ref "LED76") (pin "2") (pinfunction "RED_A_2") (pintype "bidirectional"))
      (node (ref "R77") (pin "2") (pinfunction "2_2") (pintype "passive"))
    )
    (net (code "252") (name "Net-(LED76-RED_C)") (class "Default")
      (node (ref "LED76") (pin "5") (pinfunction "RED_C_5") (pintype "bidirectional"))
      (node (ref "LED77") (pin "2") (pinfunction "RED_A_2") (pintype "bidirectional"))
    )
    (net (code "253") (name "Net-(LED77-BLUE_C)") (class "Default")
      (node (ref "LED77") (pin "4") (pinfunction "BLUE_C_4") (pintype "bidirectional"))
      (node (ref "LED78") (pin "3") (pinfunction "BLUE_A_3") (pintype "bidirectional"))
    )
    (net (code "254") (name "Net-(LED77-GREEN_C)") (class "Default")
      (node (ref "LED77") (pin "6") (pinfunction "GREEN_C_6") (pintype "bidirectional"))
      (node (ref "LED78") (pin "1") (pinfunction "GREEN_A_1") (pintype "bidirectional"))
    )
    (net (code "255") (name "Net-(LED77-RED_C)") (class "Default")
      (node (ref "LED77") (pin "5") (pinfunction "RED_C_5") (pintype "bidirectional"))
      (node (ref "LED78") (pin "2") (pinfunction "RED_A_2") (pintype "bidirectional"))
    )
    (net (code "256") (name "Net-(LED79-BLUE_A)") (class "Default")
      (node (ref "LED79") (pin "3") (pinfunction "BLUE_A_3") (pintype "bidirectional"))
      (node (ref "R78") (pin "2") (pinfunction "2_2") (pintype "passive"))
    )
    (net (code "257") (name "Net-(LED79-BLUE_C)") (class "Default")
      (node (ref "LED79") (pin "4") (pinfunction "BLUE_C_4") (pintype "bidirectional"))
      (node (ref "LED80") (pin "3") (pinfunction "BLUE_A_3") (pintype "bidirectional"))
    )
    (net (code "258") (name "Net-(LED79-GREEN_A)") (class "Default")
      (node (ref "LED79") (pin "1") (pinfunction "GREEN_A_1") (pintype "bidirectional"))
      (node (ref "R79") (pin "2") (pinfunction "2_2") (pintype "passive"))
    )
    (net (code "259") (name "Net-(LED79-GREEN_C)") (class "Default")
      (node (ref "LED79") (pin "6") (pinfunction "GREEN_C_6") (pintype "bidirectional"))
      (node (ref "LED80") (pin "1") (pinfunction "GREEN_A_1") (pintype "bidirectional"))
    )
    (net (code "260") (name "Net-(LED79-RED_A)") (class "Default")
      (node (ref "LED79") (pin "2") (pinfunction "RED_A_2") (pintype "bidirectional"))
      (node (ref "R80") (pin "2") (pinfunction "2_2") (pintype "passive"))
    )
    (net (code "261") (name "Net-(LED79-RED_C)") (class "Default")
      (node (ref "LED79") (pin "5") (pinfunction "RED_C_5") (pintype "bidirectional"))
      (node (ref "LED80") (pin "2") (pinfunction "RED_A_2") (pintype "bidirectional"))
    )
    (net (code "262") (name "Net-(LED80-BLUE_C)") (class "Default")
      (node (ref "LED80") (pin "4") (pinfunction "BLUE_C_4") (pintype "bidirectional"))
      (node (ref "LED81") (pin "3") (pinfunction "BLUE_A_3") (pintype "bidirectional"))
    )
    (net (code "263") (name "Net-(LED80-GREEN_C)") (class "Default")
      (node (ref "LED80") (pin "6") (pinfunction "GREEN_C_6") (pintype "bidirectional"))
      (node (ref "LED81") (pin "1") (pinfunction "GREEN_A_1") (pintype "bidirectional"))
    )
    (net (code "264") (name "Net-(LED80-RED_C)") (class "Default")
      (node (ref "LED80") (pin "5") (pinfunction "RED_C_5") (pintype "bidirectional"))
      (node (ref "LED81") (pin "2") (pinfunction "RED_A_2") (pintype "bidirectional"))
    )
    (net (code "265") (name "Net-(LED82-BLUE_A)") (class "Default")
      (node (ref "LED82") (pin "3") (pinfunction "BLUE_A_3") (pintype "bidirectional"))
      (node (ref "R81") (pin "2") (pinfunction "2_2") (pintype "passive"))
    )
    (net (code "266") (name "Net-(LED82-BLUE_C)") (class "Default")
      (node (ref "LED82") (pin "4") (pinfunction "BLUE_C_4") (pintype "bidirectional"))
      (node (ref "LED83") (pin "3") (pinfunction "BLUE_A_3") (pintype "bidirectional"))
    )
    (net (code "267") (name "Net-(LED82-GREEN_A)") (class "Default")
      (node (ref "LED82") (pin "1") (pinfunction "GREEN_A_1") (pintype "bidirectional"))
      (node (ref "R82") (pin "2") (pinfunction "2_2") (pintype "passive"))
    )
    (net (code "268") (name "Net-(LED82-GREEN_C)") (class "Default")
      (node (ref "LED82") (pin "6") (pinfunction "GREEN_C_6") (pintype "bidirectional"))
      (node (ref "LED83") (pin "1") (pinfunction "GREEN_A_1") (pintype "bidirectional"))
    )
    (net (code "269") (name "Net-(LED82-RED_A)") (class "Default")
      (node (ref "LED82") (pin "2") (pinfunction "RED_A_2") (pintype "bidirectional"))
      (node (ref "R83") (pin "2") (pinfunction "2_2") (pintype "passive"))
    )
    (net (code "270") (name "Net-(LED82-RED_C)") (class "Default")
      (node (ref "LED82") (pin "5") (pinfunction "RED_C_5") (pintype "bidirectional"))
      (node (ref "LED83") (pin "2") (pinfunction "RED_A_2") (pintype "bidirectional"))
    )
    (net (code "271") (name "Net-(LED83-BLUE_C)") (class "Default")
      (node (ref "LED83") (pin "4") (pinfunction "BLUE_C_4") (pintype "bidirectional"))
      (node (ref "LED84") (pin "3") (pinfunction "BLUE_A_3") (pintype "bidirectional"))
    )
    (net (code "272") (name "Net-(LED83-GREEN_C)") (class "Default")
      (node (ref "LED83") (pin "6") (pinfunction "GREEN_C_6") (pintype "bidirectional"))
      (node (ref "LED84") (pin "1") (pinfunction "GREEN_A_1") (pintype "bidirectional"))
    )
    (net (code "273") (name "Net-(LED83-RED_C)") (class "Default")
      (node (ref "LED83") (pin "5") (pinfunction "RED_C_5") (pintype "bidirectional"))
      (node (ref "LED84") (pin "2") (pinfunction "RED_A_2") (pintype "bidirectional"))
    )
    (net (code "274") (name "Net-(M1-G)") (class "Default")
      (node (ref "M1") (pin "1") (pinfunction "G_1") (pintype "passive"))
      (node (ref "R11") (pin "2") (pinfunction "2_2") (pintype "passive"))
      (node (ref "R15") (pin "1") (pinfunction "1_1") (pintype "passive"))
    )
    (net (code "275") (name "Net-(M2-G)") (class "Default")
      (node (ref "M2") (pin "1") (pinfunction "G_1") (pintype "passive"))
      (node (ref "R3") (pin "2") (pinfunction "2_2") (pintype "passive"))
      (node (ref "R4") (pin "1") (pinfunction "1_1") (pintype "passive"))
    )
    (net (code "276") (name "Net-(M3-G)") (class "Default")
      (node (ref "M3") (pin "1") (pinfunction "G_1") (pintype "passive"))
      (node (ref "R5") (pin "2") (pinfunction "2_2") (pintype "passive"))
      (node (ref "R6") (pin "1") (pinfunction "1_1") (pintype "passive"))
    )
    (net (code "277") (name "Net-(U$2-CH_PD)") (class "Default")
      (node (ref "R28") (pin "2") (pinfunction "2_2") (pintype "passive"))
      (node (ref "U$2") (pin "11") (pinfunction "CH_PD_11") (pintype "bidirectional"))
    )
  )
)
